# VISHIPEL_ver1_2.net
KiCad netlist of a schematic drawn in Altium Designer
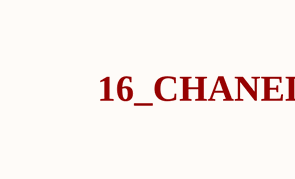
[diagram p0: VISHIPEL_ver1.2.SchDoc, top left]
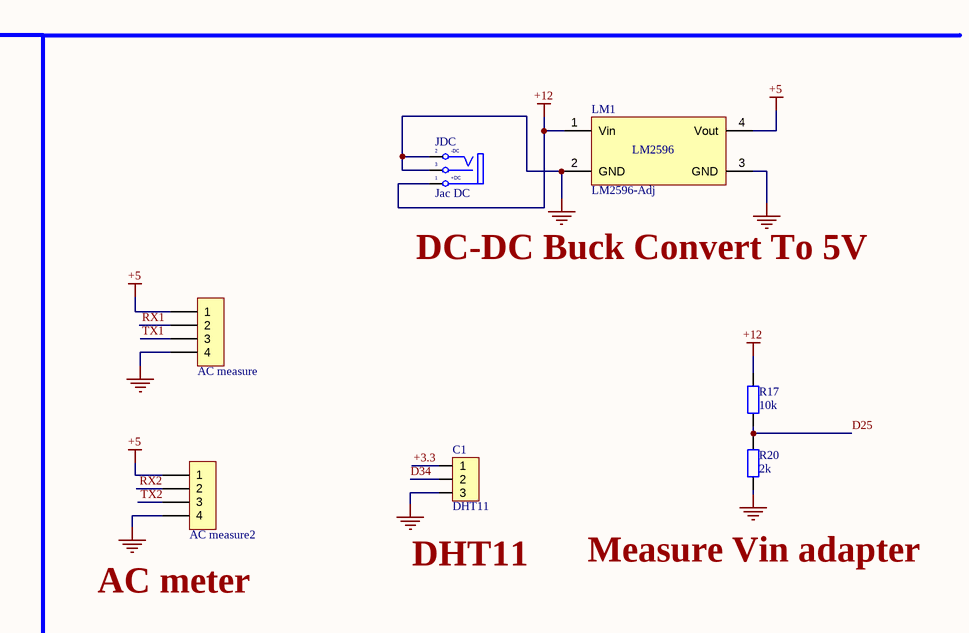
[diagram p1: VISHIPEL_ver1.2.SchDoc, top right]
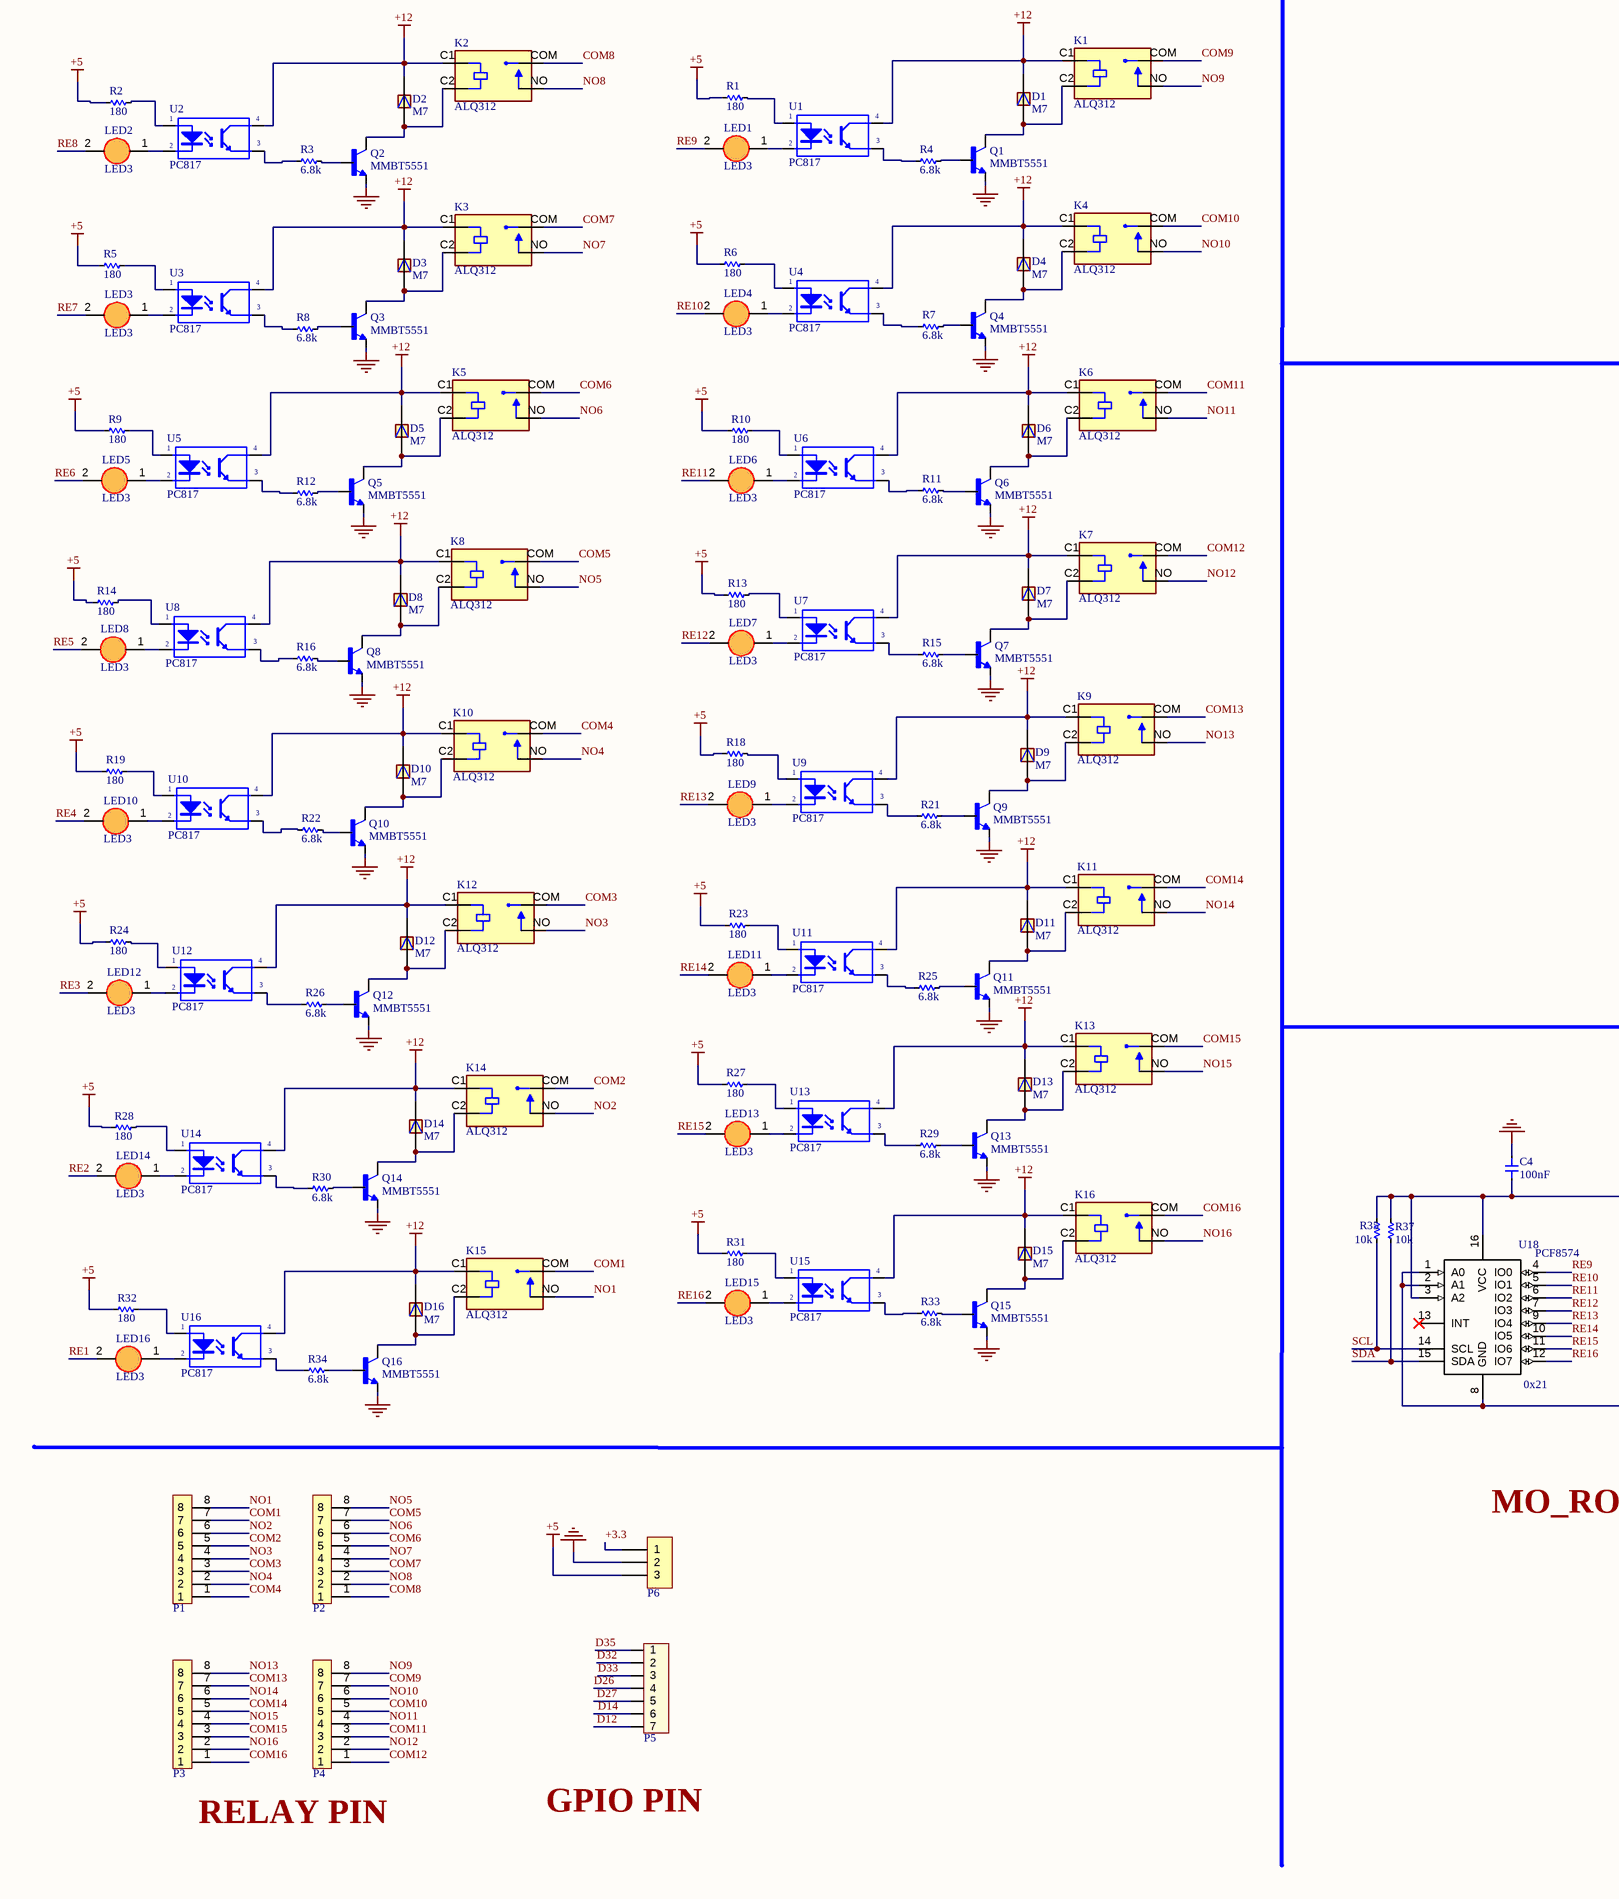
[diagram p2: VISHIPEL_ver1.2.SchDoc, bottom left]
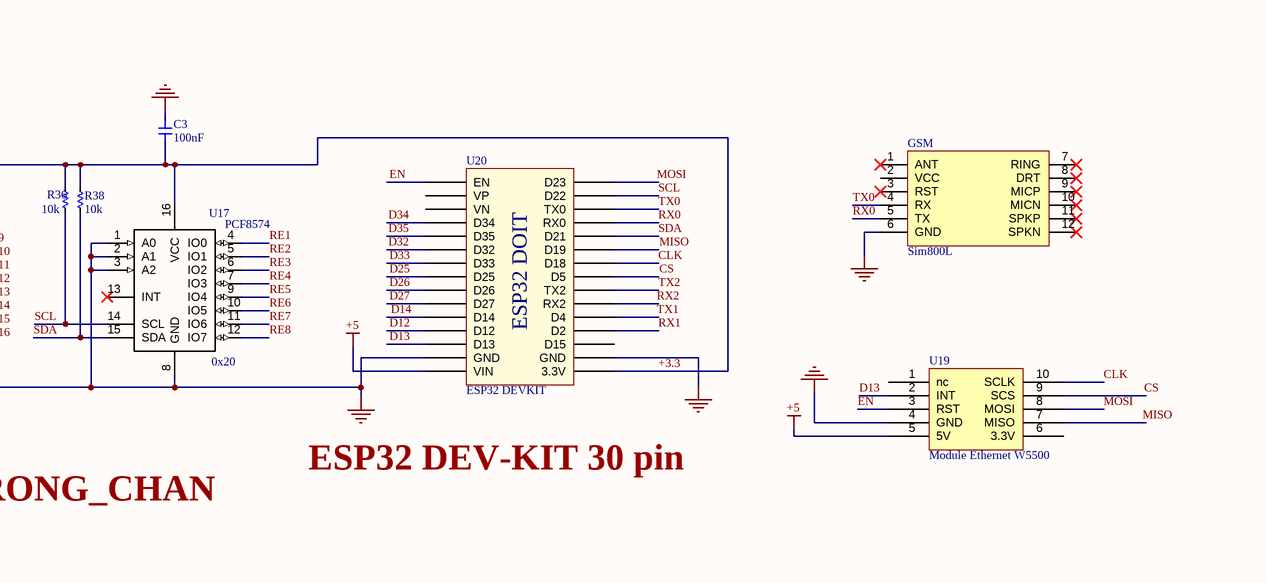
[diagram p3: VISHIPEL_ver1.2.SchDoc, bottom right]

(export (version "E")
  (design (tool "Eeschema 10.0.6"))
  (components
    (comp (ref "C1")
      (value "DHT11")
      (footprint "Header3")
      (description "Header IDC, 3 x 1 Pin Vertical 2.54mm Pitch (Non-Boxed, Male)")
      (fields
        (field (name "MANUFACTURER") "Würth Elektronik eiSos GmbH")
        (field (name "PARTNO") "613002143121")
        (field (name "CREATED BY") "Karrer Zheng")
      )
      (libsource (lib "My Library") (part "Header3"))
    )
    (comp (ref "C3")
      (value "100nF")
      (footprint "Cap 0805")
      (description "Capacitor SMD 0805")
      (libsource (lib "Altium_Lib_by_KhueNguyenCreator") (part "Cap 0805"))
    )
    (comp (ref "C4")
      (value "100nF")
      (footprint "Cap 0805")
      (description "Capacitor SMD 0805")
      (libsource (lib "Altium_Lib_by_KhueNguyenCreator") (part "Cap 0805"))
    )
    (comp (ref "D1")
      (value "M7")
      (footprint "DIOM505270X240")
      (description "Diode, SMA, 1000V, 1A, 150Â°C")
      (fields (field (name "MF") "Diotec Semiconductor"))
      (libsource (lib "M7") (part "M7"))
    )
    (comp (ref "D2")
      (value "M7")
      (footprint "DIOM505270X240")
      (description "Diode, SMA, 1000V, 1A, 150Â°C")
      (fields (field (name "MF") "Diotec Semiconductor"))
      (libsource (lib "M7") (part "M7"))
    )
    (comp (ref "D3")
      (value "M7")
      (footprint "DIOM505270X240")
      (description "Diode, SMA, 1000V, 1A, 150Â°C")
      (fields (field (name "MF") "Diotec Semiconductor"))
      (libsource (lib "M7") (part "M7"))
    )
    (comp (ref "D4")
      (value "M7")
      (footprint "DIOM505270X240")
      (description "Diode, SMA, 1000V, 1A, 150Â°C")
      (fields (field (name "MF") "Diotec Semiconductor"))
      (libsource (lib "M7") (part "M7"))
    )
    (comp (ref "D5")
      (value "M7")
      (footprint "DIOM505270X240")
      (description "Diode, SMA, 1000V, 1A, 150Â°C")
      (fields (field (name "MF") "Diotec Semiconductor"))
      (libsource (lib "M7") (part "M7"))
    )
    (comp (ref "D6")
      (value "M7")
      (footprint "DIOM505270X240")
      (description "Diode, SMA, 1000V, 1A, 150Â°C")
      (fields (field (name "MF") "Diotec Semiconductor"))
      (libsource (lib "M7") (part "M7"))
    )
    (comp (ref "D7")
      (value "M7")
      (footprint "DIOM505270X240")
      (description "Diode, SMA, 1000V, 1A, 150Â°C")
      (fields (field (name "MF") "Diotec Semiconductor"))
      (libsource (lib "M7") (part "M7"))
    )
    (comp (ref "D8")
      (value "M7")
      (footprint "DIOM505270X240")
      (description "Diode, SMA, 1000V, 1A, 150Â°C")
      (fields (field (name "MF") "Diotec Semiconductor"))
      (libsource (lib "M7") (part "M7"))
    )
    (comp (ref "D9")
      (value "M7")
      (footprint "DIOM505270X240")
      (description "Diode, SMA, 1000V, 1A, 150Â°C")
      (fields (field (name "MF") "Diotec Semiconductor"))
      (libsource (lib "M7") (part "M7"))
    )
    (comp (ref "D10")
      (value "M7")
      (footprint "DIOM505270X240")
      (description "Diode, SMA, 1000V, 1A, 150Â°C")
      (fields (field (name "MF") "Diotec Semiconductor"))
      (libsource (lib "M7") (part "M7"))
    )
    (comp (ref "D11")
      (value "M7")
      (footprint "DIOM505270X240")
      (description "Diode, SMA, 1000V, 1A, 150Â°C")
      (fields (field (name "MF") "Diotec Semiconductor"))
      (libsource (lib "M7") (part "M7"))
    )
    (comp (ref "D12")
      (value "M7")
      (footprint "DIOM505270X240")
      (description "Diode, SMA, 1000V, 1A, 150Â°C")
      (fields (field (name "MF") "Diotec Semiconductor"))
      (libsource (lib "M7") (part "M7"))
    )
    (comp (ref "D13")
      (value "M7")
      (footprint "DIOM505270X240")
      (description "Diode, SMA, 1000V, 1A, 150Â°C")
      (fields (field (name "MF") "Diotec Semiconductor"))
      (libsource (lib "M7") (part "M7"))
    )
    (comp (ref "D14")
      (value "M7")
      (footprint "DIOM505270X240")
      (description "Diode, SMA, 1000V, 1A, 150Â°C")
      (fields (field (name "MF") "Diotec Semiconductor"))
      (libsource (lib "M7") (part "M7"))
    )
    (comp (ref "D15")
      (value "M7")
      (footprint "DIOM505270X240")
      (description "Diode, SMA, 1000V, 1A, 150Â°C")
      (fields (field (name "MF") "Diotec Semiconductor"))
      (libsource (lib "M7") (part "M7"))
    )
    (comp (ref "D16")
      (value "M7")
      (footprint "DIOM505270X240")
      (description "Diode, SMA, 1000V, 1A, 150Â°C")
      (fields (field (name "MF") "Diotec Semiconductor"))
      (libsource (lib "M7") (part "M7"))
    )
    (comp (ref "GSM")
      (value "Sim800L")
      (footprint "Sim800L")
      (libsource (lib "Sim800L_Module") (part "Sim800L"))
    )
    (comp (ref "H1")
      (value "AC measure")
      (footprint "XH2.54M-4")
      (description "Cắm")
      (libsource (lib "Altium_Lib_by_KhueNguyenCreator") (part "Header 4P 2.54 Duc Thang"))
    )
    (comp (ref "H2")
      (value "AC measure2")
      (footprint "XH2.54M-4")
      (description "Cắm")
      (libsource (lib "Altium_Lib_by_KhueNguyenCreator") (part "Header 4P 2.54 Duc Thang"))
    )
    (comp (ref "H3")
      (value "P6")
      (footprint "VH3.96M-3")
      (description "Cắm")
      (libsource (lib "Altium_Lib_by_KhueNguyenCreator") (part "Header 3P VH3.96 Duc Thang"))
    )
    (comp (ref "H4")
      (value "P5")
      (footprint "VH3.96M-7")
      (description "Cắm")
      (libsource (lib "Altium_Lib_by_KhueNguyenCreator") (part "Header 7P VH3.96 Duc Thang"))
    )
    (comp (ref "JDC")
      (value "Jac DC")
      (footprint "DC-IN")
      (description "Jac DC input")
      (libsource (lib "Cty1") (part "DCIN"))
    )
    (comp (ref "K1")
      (value "ALQ312")
      (footprint "RELAY_ALQ312")
      (description "General Purpose Relay SPST-NO (1 Form A) 12VDC Coil Through Hole")
      (fields (field (name "MF") "Panasonic Electric"))
      (libsource (lib "ALQ312") (part "ALQ312"))
    )
    (comp (ref "K2")
      (value "ALQ312")
      (footprint "RELAY_ALQ312")
      (description "General Purpose Relay SPST-NO (1 Form A) 12VDC Coil Through Hole")
      (fields (field (name "MF") "Panasonic Electric"))
      (libsource (lib "ALQ312") (part "ALQ312"))
    )
    (comp (ref "K3")
      (value "ALQ312")
      (footprint "RELAY_ALQ312")
      (description "General Purpose Relay SPST-NO (1 Form A) 12VDC Coil Through Hole")
      (fields (field (name "MF") "Panasonic Electric"))
      (libsource (lib "ALQ312") (part "ALQ312"))
    )
    (comp (ref "K4")
      (value "ALQ312")
      (footprint "RELAY_ALQ312")
      (description "General Purpose Relay SPST-NO (1 Form A) 12VDC Coil Through Hole")
      (fields (field (name "MF") "Panasonic Electric"))
      (libsource (lib "ALQ312") (part "ALQ312"))
    )
    (comp (ref "K5")
      (value "ALQ312")
      (footprint "RELAY_ALQ312")
      (description "General Purpose Relay SPST-NO (1 Form A) 12VDC Coil Through Hole")
      (fields (field (name "MF") "Panasonic Electric"))
      (libsource (lib "ALQ312") (part "ALQ312"))
    )
    (comp (ref "K6")
      (value "ALQ312")
      (footprint "RELAY_ALQ312")
      (description "General Purpose Relay SPST-NO (1 Form A) 12VDC Coil Through Hole")
      (fields (field (name "MF") "Panasonic Electric"))
      (libsource (lib "ALQ312") (part "ALQ312"))
    )
    (comp (ref "K7")
      (value "ALQ312")
      (footprint "RELAY_ALQ312")
      (description "General Purpose Relay SPST-NO (1 Form A) 12VDC Coil Through Hole")
      (fields (field (name "MF") "Panasonic Electric"))
      (libsource (lib "ALQ312") (part "ALQ312"))
    )
    (comp (ref "K8")
      (value "ALQ312")
      (footprint "RELAY_ALQ312")
      (description "General Purpose Relay SPST-NO (1 Form A) 12VDC Coil Through Hole")
      (fields (field (name "MF") "Panasonic Electric"))
      (libsource (lib "ALQ312") (part "ALQ312"))
    )
    (comp (ref "K9")
      (value "ALQ312")
      (footprint "RELAY_ALQ312")
      (description "General Purpose Relay SPST-NO (1 Form A) 12VDC Coil Through Hole")
      (fields (field (name "MF") "Panasonic Electric"))
      (libsource (lib "ALQ312") (part "ALQ312"))
    )
    (comp (ref "K10")
      (value "ALQ312")
      (footprint "RELAY_ALQ312")
      (description "General Purpose Relay SPST-NO (1 Form A) 12VDC Coil Through Hole")
      (fields (field (name "MF") "Panasonic Electric"))
      (libsource (lib "ALQ312") (part "ALQ312"))
    )
    (comp (ref "K11")
      (value "ALQ312")
      (footprint "RELAY_ALQ312")
      (description "General Purpose Relay SPST-NO (1 Form A) 12VDC Coil Through Hole")
      (fields (field (name "MF") "Panasonic Electric"))
      (libsource (lib "ALQ312") (part "ALQ312"))
    )
    (comp (ref "K12")
      (value "ALQ312")
      (footprint "RELAY_ALQ312")
      (description "General Purpose Relay SPST-NO (1 Form A) 12VDC Coil Through Hole")
      (fields (field (name "MF") "Panasonic Electric"))
      (libsource (lib "ALQ312") (part "ALQ312"))
    )
    (comp (ref "K13")
      (value "ALQ312")
      (footprint "RELAY_ALQ312")
      (description "General Purpose Relay SPST-NO (1 Form A) 12VDC Coil Through Hole")
      (fields (field (name "MF") "Panasonic Electric"))
      (libsource (lib "ALQ312") (part "ALQ312"))
    )
    (comp (ref "K14")
      (value "ALQ312")
      (footprint "RELAY_ALQ312")
      (description "General Purpose Relay SPST-NO (1 Form A) 12VDC Coil Through Hole")
      (fields (field (name "MF") "Panasonic Electric"))
      (libsource (lib "ALQ312") (part "ALQ312"))
    )
    (comp (ref "K15")
      (value "ALQ312")
      (footprint "RELAY_ALQ312")
      (description "General Purpose Relay SPST-NO (1 Form A) 12VDC Coil Through Hole")
      (fields (field (name "MF") "Panasonic Electric"))
      (libsource (lib "ALQ312") (part "ALQ312"))
    )
    (comp (ref "K16")
      (value "ALQ312")
      (footprint "RELAY_ALQ312")
      (description "General Purpose Relay SPST-NO (1 Form A) 12VDC Coil Through Hole")
      (fields (field (name "MF") "Panasonic Electric"))
      (libsource (lib "ALQ312") (part "ALQ312"))
    )
    (comp (ref "LED1")
      (value "LED3")
      (footprint "LED3mm")
      (description "LED 3mm")
      (libsource (lib "My Library") (part "LED 3mm"))
    )
    (comp (ref "LED2")
      (value "LED3")
      (footprint "LED3mm")
      (description "LED 3mm")
      (libsource (lib "My Library") (part "LED 3mm"))
    )
    (comp (ref "LED3")
      (value "LED3")
      (footprint "LED3mm")
      (description "LED 3mm")
      (libsource (lib "My Library") (part "LED 3mm"))
    )
    (comp (ref "LED4")
      (value "LED3")
      (footprint "LED3mm")
      (description "LED 3mm")
      (libsource (lib "My Library") (part "LED 3mm"))
    )
    (comp (ref "LED5")
      (value "LED3")
      (footprint "LED3mm")
      (description "LED 3mm")
      (libsource (lib "My Library") (part "LED 3mm"))
    )
    (comp (ref "LED6")
      (value "LED3")
      (footprint "LED3mm")
      (description "LED 3mm")
      (libsource (lib "My Library") (part "LED 3mm"))
    )
    (comp (ref "LED7")
      (value "LED3")
      (footprint "LED3mm")
      (description "LED 3mm")
      (libsource (lib "My Library") (part "LED 3mm"))
    )
    (comp (ref "LED8")
      (value "LED3")
      (footprint "LED3mm")
      (description "LED 3mm")
      (libsource (lib "My Library") (part "LED 3mm"))
    )
    (comp (ref "LED9")
      (value "LED3")
      (footprint "LED3mm")
      (description "LED 3mm")
      (libsource (lib "My Library") (part "LED 3mm"))
    )
    (comp (ref "LED10")
      (value "LED3")
      (footprint "LED3mm")
      (description "LED 3mm")
      (libsource (lib "My Library") (part "LED 3mm"))
    )
    (comp (ref "LED11")
      (value "LED3")
      (footprint "LED3mm")
      (description "LED 3mm")
      (libsource (lib "My Library") (part "LED 3mm"))
    )
    (comp (ref "LED12")
      (value "LED3")
      (footprint "LED3mm")
      (description "LED 3mm")
      (libsource (lib "My Library") (part "LED 3mm"))
    )
    (comp (ref "LED13")
      (value "LED3")
      (footprint "LED3mm")
      (description "LED 3mm")
      (libsource (lib "My Library") (part "LED 3mm"))
    )
    (comp (ref "LED14")
      (value "LED3")
      (footprint "LED3mm")
      (description "LED 3mm")
      (libsource (lib "My Library") (part "LED 3mm"))
    )
    (comp (ref "LED15")
      (value "LED3")
      (footprint "LED3mm")
      (description "LED 3mm")
      (libsource (lib "My Library") (part "LED 3mm"))
    )
    (comp (ref "LED16")
      (value "LED3")
      (footprint "LED3mm")
      (description "LED 3mm")
      (libsource (lib "My Library") (part "LED 3mm"))
    )
    (comp (ref "LM1")
      (value "LM2596-Adj")
      (footprint "lm2596")
      (description "Designed By @Alixahedi")
      (libsource (lib "LM2596-Adj") (part "LM2596-Adj"))
    )
    (comp (ref "P1")
      (value "BIG Heager 8")
      (footprint "BIG_Header 8")
      (libsource (lib "Cty1") (part "BIG_Header 8"))
    )
    (comp (ref "P2")
      (value "BIG Heager 8")
      (footprint "BIG_Header 8")
      (libsource (lib "Cty1") (part "BIG_Header 8"))
    )
    (comp (ref "P3")
      (value "BIG Heager 8")
      (footprint "BIG_Header 8")
      (libsource (lib "Cty1") (part "BIG_Header 8"))
    )
    (comp (ref "P4")
      (value "BIG Heager 8")
      (footprint "BIG_Header 8")
      (libsource (lib "Cty1") (part "BIG_Header 8"))
    )
    (comp (ref "Q1")
      (value "MMBT5551")
      (footprint "SOT23-3")
      (fields (field (name "MF") "Fairchild Semiconductor"))
      (libsource (lib "MMBT5551") (part "MMBT5551"))
    )
    (comp (ref "Q2")
      (value "MMBT5551")
      (footprint "SOT23-3")
      (fields (field (name "MF") "Fairchild Semiconductor"))
      (libsource (lib "MMBT5551") (part "MMBT5551"))
    )
    (comp (ref "Q3")
      (value "MMBT5551")
      (footprint "SOT23-3")
      (fields (field (name "MF") "Fairchild Semiconductor"))
      (libsource (lib "MMBT5551") (part "MMBT5551"))
    )
    (comp (ref "Q4")
      (value "MMBT5551")
      (footprint "SOT23-3")
      (fields (field (name "MF") "Fairchild Semiconductor"))
      (libsource (lib "MMBT5551") (part "MMBT5551"))
    )
    (comp (ref "Q5")
      (value "MMBT5551")
      (footprint "SOT23-3")
      (fields (field (name "MF") "Fairchild Semiconductor"))
      (libsource (lib "MMBT5551") (part "MMBT5551"))
    )
    (comp (ref "Q6")
      (value "MMBT5551")
      (footprint "SOT23-3")
      (fields (field (name "MF") "Fairchild Semiconductor"))
      (libsource (lib "MMBT5551") (part "MMBT5551"))
    )
    (comp (ref "Q7")
      (value "MMBT5551")
      (footprint "SOT23-3")
      (fields (field (name "MF") "Fairchild Semiconductor"))
      (libsource (lib "MMBT5551") (part "MMBT5551"))
    )
    (comp (ref "Q8")
      (value "MMBT5551")
      (footprint "SOT23-3")
      (fields (field (name "MF") "Fairchild Semiconductor"))
      (libsource (lib "MMBT5551") (part "MMBT5551"))
    )
    (comp (ref "Q9")
      (value "MMBT5551")
      (footprint "SOT23-3")
      (fields (field (name "MF") "Fairchild Semiconductor"))
      (libsource (lib "MMBT5551") (part "MMBT5551"))
    )
    (comp (ref "Q10")
      (value "MMBT5551")
      (footprint "SOT23-3")
      (fields (field (name "MF") "Fairchild Semiconductor"))
      (libsource (lib "MMBT5551") (part "MMBT5551"))
    )
    (comp (ref "Q11")
      (value "MMBT5551")
      (footprint "SOT23-3")
      (fields (field (name "MF") "Fairchild Semiconductor"))
      (libsource (lib "MMBT5551") (part "MMBT5551"))
    )
    (comp (ref "Q12")
      (value "MMBT5551")
      (footprint "SOT23-3")
      (fields (field (name "MF") "Fairchild Semiconductor"))
      (libsource (lib "MMBT5551") (part "MMBT5551"))
    )
    (comp (ref "Q13")
      (value "MMBT5551")
      (footprint "SOT23-3")
      (fields (field (name "MF") "Fairchild Semiconductor"))
      (libsource (lib "MMBT5551") (part "MMBT5551"))
    )
    (comp (ref "Q14")
      (value "MMBT5551")
      (footprint "SOT23-3")
      (fields (field (name "MF") "Fairchild Semiconductor"))
      (libsource (lib "MMBT5551") (part "MMBT5551"))
    )
    (comp (ref "Q15")
      (value "MMBT5551")
      (footprint "SOT23-3")
      (fields (field (name "MF") "Fairchild Semiconductor"))
      (libsource (lib "MMBT5551") (part "MMBT5551"))
    )
    (comp (ref "Q16")
      (value "MMBT5551")
      (footprint "SOT23-3")
      (fields (field (name "MF") "Fairchild Semiconductor"))
      (libsource (lib "MMBT5551") (part "MMBT5551"))
    )
    (comp (ref "R1")
      (value "180")
      (footprint "RES-SMD-0101")
      (description "Resistor")
      (fields
        (field (name "MANUFACTURER") "Generic Components")
        (field (name "PUBLISHER") "Altium Hobart Technology Centre")
      )
      (libsource (lib "My Library") (part "Res-SMD"))
    )
    (comp (ref "R2")
      (value "180")
      (footprint "RES-SMD-0101")
      (description "Resistor")
      (fields
        (field (name "MANUFACTURER") "Generic Components")
        (field (name "PUBLISHER") "Altium Hobart Technology Centre")
      )
      (libsource (lib "My Library") (part "Res-SMD"))
    )
    (comp (ref "R3")
      (value "6.8k")
      (footprint "RES-SMD-0101")
      (description "Resistor")
      (fields
        (field (name "MANUFACTURER") "Generic Components")
        (field (name "PUBLISHER") "Altium Hobart Technology Centre")
      )
      (libsource (lib "My Library") (part "Res-SMD"))
    )
    (comp (ref "R4")
      (value "6.8k")
      (footprint "RES-SMD-0101")
      (description "Resistor")
      (fields
        (field (name "MANUFACTURER") "Generic Components")
        (field (name "PUBLISHER") "Altium Hobart Technology Centre")
      )
      (libsource (lib "My Library") (part "Res-SMD"))
    )
    (comp (ref "R5")
      (value "180")
      (footprint "RES-SMD-0101")
      (description "Resistor")
      (fields
        (field (name "MANUFACTURER") "Generic Components")
        (field (name "PUBLISHER") "Altium Hobart Technology Centre")
      )
      (libsource (lib "My Library") (part "Res-SMD"))
    )
    (comp (ref "R6")
      (value "180")
      (footprint "RES-SMD-0101")
      (description "Resistor")
      (fields
        (field (name "MANUFACTURER") "Generic Components")
        (field (name "PUBLISHER") "Altium Hobart Technology Centre")
      )
      (libsource (lib "My Library") (part "Res-SMD"))
    )
    (comp (ref "R7")
      (value "6.8k")
      (footprint "RES-SMD-0101")
      (description "Resistor")
      (fields
        (field (name "MANUFACTURER") "Generic Components")
        (field (name "PUBLISHER") "Altium Hobart Technology Centre")
      )
      (libsource (lib "My Library") (part "Res-SMD"))
    )
    (comp (ref "R8")
      (value "6.8k")
      (footprint "RES-SMD-0101")
      (description "Resistor")
      (fields
        (field (name "MANUFACTURER") "Generic Components")
        (field (name "PUBLISHER") "Altium Hobart Technology Centre")
      )
      (libsource (lib "My Library") (part "Res-SMD"))
    )
    (comp (ref "R9")
      (value "180")
      (footprint "RES-SMD-0101")
      (description "Resistor")
      (fields
        (field (name "MANUFACTURER") "Generic Components")
        (field (name "PUBLISHER") "Altium Hobart Technology Centre")
      )
      (libsource (lib "My Library") (part "Res-SMD"))
    )
    (comp (ref "R10")
      (value "180")
      (footprint "RES-SMD-0101")
      (description "Resistor")
      (fields
        (field (name "MANUFACTURER") "Generic Components")
        (field (name "PUBLISHER") "Altium Hobart Technology Centre")
      )
      (libsource (lib "My Library") (part "Res-SMD"))
    )
    (comp (ref "R11")
      (value "6.8k")
      (footprint "RES-SMD-0101")
      (description "Resistor")
      (fields
        (field (name "MANUFACTURER") "Generic Components")
        (field (name "PUBLISHER") "Altium Hobart Technology Centre")
      )
      (libsource (lib "My Library") (part "Res-SMD"))
    )
    (comp (ref "R12")
      (value "6.8k")
      (footprint "RES-SMD-0101")
      (description "Resistor")
      (fields
        (field (name "MANUFACTURER") "Generic Components")
        (field (name "PUBLISHER") "Altium Hobart Technology Centre")
      )
      (libsource (lib "My Library") (part "Res-SMD"))
    )
    (comp (ref "R13")
      (value "180")
      (footprint "RES-SMD-0101")
      (description "Resistor")
      (fields
        (field (name "MANUFACTURER") "Generic Components")
        (field (name "PUBLISHER") "Altium Hobart Technology Centre")
      )
      (libsource (lib "My Library") (part "Res-SMD"))
    )
    (comp (ref "R14")
      (value "180")
      (footprint "RES-SMD-0101")
      (description "Resistor")
      (fields
        (field (name "MANUFACTURER") "Generic Components")
        (field (name "PUBLISHER") "Altium Hobart Technology Centre")
      )
      (libsource (lib "My Library") (part "Res-SMD"))
    )
    (comp (ref "R15")
      (value "6.8k")
      (footprint "RES-SMD-0101")
      (description "Resistor")
      (fields
        (field (name "MANUFACTURER") "Generic Components")
        (field (name "PUBLISHER") "Altium Hobart Technology Centre")
      )
      (libsource (lib "My Library") (part "Res-SMD"))
    )
    (comp (ref "R16")
      (value "6.8k")
      (footprint "RES-SMD-0101")
      (description "Resistor")
      (fields
        (field (name "MANUFACTURER") "Generic Components")
        (field (name "PUBLISHER") "Altium Hobart Technology Centre")
      )
      (libsource (lib "My Library") (part "Res-SMD"))
    )
    (comp (ref "R17")
      (value "10k")
      (footprint "DIEN TRO 1/4 W")
      (description "Resistor")
      (fields (field (name "Comment") "R0.4W") (field (name "PUBLISHER") "Altium Limited"))
      (libsource (lib "My Library") (part "Res 1/4 W"))
    )
    (comp (ref "R18")
      (value "180")
      (footprint "RES-SMD-0101")
      (description "Resistor")
      (fields
        (field (name "MANUFACTURER") "Generic Components")
        (field (name "PUBLISHER") "Altium Hobart Technology Centre")
      )
      (libsource (lib "My Library") (part "Res-SMD"))
    )
    (comp (ref "R19")
      (value "180")
      (footprint "RES-SMD-0101")
      (description "Resistor")
      (fields
        (field (name "MANUFACTURER") "Generic Components")
        (field (name "PUBLISHER") "Altium Hobart Technology Centre")
      )
      (libsource (lib "My Library") (part "Res-SMD"))
    )
    (comp (ref "R20")
      (value "2k")
      (footprint "DIEN TRO 1/4 W")
      (description "Resistor")
      (fields (field (name "Comment") "R0.4W") (field (name "PUBLISHER") "Altium Limited"))
      (libsource (lib "My Library") (part "Res 1/4 W"))
    )
    (comp (ref "R21")
      (value "6.8k")
      (footprint "RES-SMD-0101")
      (description "Resistor")
      (fields
        (field (name "MANUFACTURER") "Generic Components")
        (field (name "PUBLISHER") "Altium Hobart Technology Centre")
      )
      (libsource (lib "My Library") (part "Res-SMD"))
    )
    (comp (ref "R22")
      (value "6.8k")
      (footprint "RES-SMD-0101")
      (description "Resistor")
      (fields
        (field (name "MANUFACTURER") "Generic Components")
        (field (name "PUBLISHER") "Altium Hobart Technology Centre")
      )
      (libsource (lib "My Library") (part "Res-SMD"))
    )
    (comp (ref "R23")
      (value "180")
      (footprint "RES-SMD-0101")
      (description "Resistor")
      (fields
        (field (name "MANUFACTURER") "Generic Components")
        (field (name "PUBLISHER") "Altium Hobart Technology Centre")
      )
      (libsource (lib "My Library") (part "Res-SMD"))
    )
    (comp (ref "R24")
      (value "180")
      (footprint "RES-SMD-0101")
      (description "Resistor")
      (fields
        (field (name "MANUFACTURER") "Generic Components")
        (field (name "PUBLISHER") "Altium Hobart Technology Centre")
      )
      (libsource (lib "My Library") (part "Res-SMD"))
    )
    (comp (ref "R25")
      (value "6.8k")
      (footprint "RES-SMD-0101")
      (description "Resistor")
      (fields
        (field (name "MANUFACTURER") "Generic Components")
        (field (name "PUBLISHER") "Altium Hobart Technology Centre")
      )
      (libsource (lib "My Library") (part "Res-SMD"))
    )
    (comp (ref "R26")
      (value "6.8k")
      (footprint "RES-SMD-0101")
      (description "Resistor")
      (fields
        (field (name "MANUFACTURER") "Generic Components")
        (field (name "PUBLISHER") "Altium Hobart Technology Centre")
      )
      (libsource (lib "My Library") (part "Res-SMD"))
    )
    (comp (ref "R27")
      (value "180")
      (footprint "RES-SMD-0101")
      (description "Resistor")
      (fields
        (field (name "MANUFACTURER") "Generic Components")
        (field (name "PUBLISHER") "Altium Hobart Technology Centre")
      )
      (libsource (lib "My Library") (part "Res-SMD"))
    )
    (comp (ref "R28")
      (value "180")
      (footprint "RES-SMD-0101")
      (description "Resistor")
      (fields
        (field (name "MANUFACTURER") "Generic Components")
        (field (name "PUBLISHER") "Altium Hobart Technology Centre")
      )
      (libsource (lib "My Library") (part "Res-SMD"))
    )
    (comp (ref "R29")
      (value "6.8k")
      (footprint "RES-SMD-0101")
      (description "Resistor")
      (fields
        (field (name "MANUFACTURER") "Generic Components")
        (field (name "PUBLISHER") "Altium Hobart Technology Centre")
      )
      (libsource (lib "My Library") (part "Res-SMD"))
    )
    (comp (ref "R30")
      (value "6.8k")
      (footprint "RES-SMD-0101")
      (description "Resistor")
      (fields
        (field (name "MANUFACTURER") "Generic Components")
        (field (name "PUBLISHER") "Altium Hobart Technology Centre")
      )
      (libsource (lib "My Library") (part "Res-SMD"))
    )
    (comp (ref "R31")
      (value "180")
      (footprint "RES-SMD-0101")
      (description "Resistor")
      (fields
        (field (name "MANUFACTURER") "Generic Components")
        (field (name "PUBLISHER") "Altium Hobart Technology Centre")
      )
      (libsource (lib "My Library") (part "Res-SMD"))
    )
    (comp (ref "R32")
      (value "180")
      (footprint "RES-SMD-0101")
      (description "Resistor")
      (fields
        (field (name "MANUFACTURER") "Generic Components")
        (field (name "PUBLISHER") "Altium Hobart Technology Centre")
      )
      (libsource (lib "My Library") (part "Res-SMD"))
    )
    (comp (ref "R33")
      (value "6.8k")
      (footprint "RES-SMD-0101")
      (description "Resistor")
      (fields
        (field (name "MANUFACTURER") "Generic Components")
        (field (name "PUBLISHER") "Altium Hobart Technology Centre")
      )
      (libsource (lib "My Library") (part "Res-SMD"))
    )
    (comp (ref "R34")
      (value "6.8k")
      (footprint "RES-SMD-0101")
      (description "Resistor")
      (fields
        (field (name "MANUFACTURER") "Generic Components")
        (field (name "PUBLISHER") "Altium Hobart Technology Centre")
      )
      (libsource (lib "My Library") (part "Res-SMD"))
    )
    (comp (ref "R35")
      (value "10k")
      (footprint "RES-SMD-0101")
      (description "Resistor")
      (fields
        (field (name "MANUFACTURER") "Generic Components")
        (field (name "PUBLISHER") "Altium Hobart Technology Centre")
      )
      (libsource (lib "My Library") (part "Res-SMD"))
    )
    (comp (ref "R36")
      (value "10k")
      (footprint "RES-SMD-0101")
      (description "Resistor")
      (fields
        (field (name "MANUFACTURER") "Generic Components")
        (field (name "PUBLISHER") "Altium Hobart Technology Centre")
      )
      (libsource (lib "My Library") (part "Res-SMD"))
    )
    (comp (ref "R37")
      (value "10k")
      (footprint "RES-SMD-0101")
      (description "Resistor")
      (fields
        (field (name "MANUFACTURER") "Generic Components")
        (field (name "PUBLISHER") "Altium Hobart Technology Centre")
      )
      (libsource (lib "My Library") (part "Res-SMD"))
    )
    (comp (ref "R38")
      (value "10k")
      (footprint "RES-SMD-0101")
      (description "Resistor")
      (fields
        (field (name "MANUFACTURER") "Generic Components")
        (field (name "PUBLISHER") "Altium Hobart Technology Centre")
      )
      (libsource (lib "My Library") (part "Res-SMD"))
    )
    (comp (ref "U1")
      (value "PC817")
      (footprint "DIP4/W0.3")
      (description "Single Opto")
      (libsource (lib "My Library") (part "PC817"))
    )
    (comp (ref "U2")
      (value "PC817")
      (footprint "DIP4/W0.3")
      (description "Single Opto")
      (libsource (lib "My Library") (part "PC817"))
    )
    (comp (ref "U3")
      (value "PC817")
      (footprint "DIP4/W0.3")
      (description "Single Opto")
      (libsource (lib "My Library") (part "PC817"))
    )
    (comp (ref "U4")
      (value "PC817")
      (footprint "DIP4/W0.3")
      (description "Single Opto")
      (libsource (lib "My Library") (part "PC817"))
    )
    (comp (ref "U5")
      (value "PC817")
      (footprint "DIP4/W0.3")
      (description "Single Opto")
      (libsource (lib "My Library") (part "PC817"))
    )
    (comp (ref "U6")
      (value "PC817")
      (footprint "DIP4/W0.3")
      (description "Single Opto")
      (libsource (lib "My Library") (part "PC817"))
    )
    (comp (ref "U7")
      (value "PC817")
      (footprint "DIP4/W0.3")
      (description "Single Opto")
      (libsource (lib "My Library") (part "PC817"))
    )
    (comp (ref "U8")
      (value "PC817")
      (footprint "DIP4/W0.3")
      (description "Single Opto")
      (libsource (lib "My Library") (part "PC817"))
    )
    (comp (ref "U9")
      (value "PC817")
      (footprint "DIP4/W0.3")
      (description "Single Opto")
      (libsource (lib "My Library") (part "PC817"))
    )
    (comp (ref "U10")
      (value "PC817")
      (footprint "DIP4/W0.3")
      (description "Single Opto")
      (libsource (lib "My Library") (part "PC817"))
    )
    (comp (ref "U11")
      (value "PC817")
      (footprint "DIP4/W0.3")
      (description "Single Opto")
      (libsource (lib "My Library") (part "PC817"))
    )
    (comp (ref "U12")
      (value "PC817")
      (footprint "DIP4/W0.3")
      (description "Single Opto")
      (libsource (lib "My Library") (part "PC817"))
    )
    (comp (ref "U13")
      (value "PC817")
      (footprint "DIP4/W0.3")
      (description "Single Opto")
      (libsource (lib "My Library") (part "PC817"))
    )
    (comp (ref "U14")
      (value "PC817")
      (footprint "DIP4/W0.3")
      (description "Single Opto")
      (libsource (lib "My Library") (part "PC817"))
    )
    (comp (ref "U15")
      (value "PC817")
      (footprint "DIP4/W0.3")
      (description "Single Opto")
      (libsource (lib "My Library") (part "PC817"))
    )
    (comp (ref "U16")
      (value "PC817")
      (footprint "DIP4/W0.3")
      (description "Single Opto")
      (libsource (lib "My Library") (part "PC817"))
    )
    (comp (ref "U17")
      (value "PCF8574")
      (footprint "DIP16")
      (description "I2C PORT EXPANDER")
      (fields
        (field (name "MANUFACTURER PART NUMBER") "PCF8574T/3,512")
        (field (name "MANUFACTURER") "NXP Semiconductors")
      )
      (libsource (lib "My Library") (part "PCF8574"))
    )
    (comp (ref "U18")
      (value "PCF8574")
      (footprint "DIP16")
      (description "I2C PORT EXPANDER")
      (fields
        (field (name "MANUFACTURER PART NUMBER") "PCF8574T/3,512")
        (field (name "MANUFACTURER") "NXP Semiconductors")
      )
      (libsource (lib "My Library") (part "PCF8574"))
    )
    (comp (ref "U19")
      (value "Module Ethernet W5500")
      (footprint "Module Ethernet W5500")
      (libsource (lib "Module Ethernet W5500") (part "Module Ethernet W5500"))
    )
    (comp (ref "U20")
      (value "ESP32 DEVKIT")
      (footprint "ESP32 WROOM 32 KIT")
      (libsource (lib "Altium_Lib_by_KhueNguyenCreator") (part "ESP32 WROOM 32 KIT"))
    )
  )
  (nets
    (net (code "1") (name "+5") (class "Default")
      (node (ref "H1") (pin "1") (pinfunction "1_1") (pintype "passive"))
      (node (ref "H2") (pin "1") (pinfunction "1_1") (pintype "passive"))
      (node (ref "H3") (pin "3") (pinfunction "3_3") (pintype "passive"))
      (node (ref "LM1") (pin "4") (pinfunction "Vout_4") (pintype "passive"))
      (node (ref "R1") (pin "1") (pinfunction "1_1") (pintype "passive"))
      (node (ref "R10") (pin "1") (pinfunction "1_1") (pintype "passive"))
      (node (ref "R13") (pin "1") (pinfunction "1_1") (pintype "passive"))
      (node (ref "R14") (pin "1") (pinfunction "1_1") (pintype "passive"))
      (node (ref "R18") (pin "1") (pinfunction "1_1") (pintype "passive"))
      (node (ref "R19") (pin "1") (pinfunction "1_1") (pintype "passive"))
      (node (ref "R2") (pin "1") (pinfunction "1_1") (pintype "passive"))
      (node (ref "R23") (pin "1") (pinfunction "1_1") (pintype "passive"))
      (node (ref "R24") (pin "1") (pinfunction "1_1") (pintype "passive"))
      (node (ref "R27") (pin "1") (pinfunction "1_1") (pintype "passive"))
      (node (ref "R28") (pin "1") (pinfunction "1_1") (pintype "passive"))
      (node (ref "R31") (pin "1") (pinfunction "1_1") (pintype "passive"))
      (node (ref "R32") (pin "1") (pinfunction "1_1") (pintype "passive"))
      (node (ref "R5") (pin "1") (pinfunction "1_1") (pintype "passive"))
      (node (ref "R6") (pin "1") (pinfunction "1_1") (pintype "passive"))
      (node (ref "R9") (pin "1") (pinfunction "1_1") (pintype "passive"))
      (node (ref "U19") (pin "5") (pinfunction "5V_5") (pintype "passive"))
      (node (ref "U20") (pin "15") (pinfunction "VIN_15") (pintype "passive"))
    )
    (net (code "2") (name "+12") (class "Default")
      (node (ref "D1") (pin "C") (pinfunction "C_C") (pintype "passive"))
      (node (ref "D10") (pin "C") (pinfunction "C_C") (pintype "passive"))
      (node (ref "D11") (pin "C") (pinfunction "C_C") (pintype "passive"))
      (node (ref "D12") (pin "C") (pinfunction "C_C") (pintype "passive"))
      (node (ref "D13") (pin "C") (pinfunction "C_C") (pintype "passive"))
      (node (ref "D14") (pin "C") (pinfunction "C_C") (pintype "passive"))
      (node (ref "D15") (pin "C") (pinfunction "C_C") (pintype "passive"))
      (node (ref "D16") (pin "C") (pinfunction "C_C") (pintype "passive"))
      (node (ref "D2") (pin "C") (pinfunction "C_C") (pintype "passive"))
      (node (ref "D3") (pin "C") (pinfunction "C_C") (pintype "passive"))
      (node (ref "D4") (pin "C") (pinfunction "C_C") (pintype "passive"))
      (node (ref "D5") (pin "C") (pinfunction "C_C") (pintype "passive"))
      (node (ref "D6") (pin "C") (pinfunction "C_C") (pintype "passive"))
      (node (ref "D7") (pin "C") (pinfunction "C_C") (pintype "passive"))
      (node (ref "D8") (pin "C") (pinfunction "C_C") (pintype "passive"))
      (node (ref "D9") (pin "C") (pinfunction "C_C") (pintype "passive"))
      (node (ref "JDC") (pin "1") (pinfunction "T_1") (pintype "passive"))
      (node (ref "K1") (pin "C1") (pinfunction "COIL1_C1") (pintype "passive"))
      (node (ref "K10") (pin "C1") (pinfunction "COIL1_C1") (pintype "passive"))
      (node (ref "K11") (pin "C1") (pinfunction "COIL1_C1") (pintype "passive"))
      (node (ref "K12") (pin "C1") (pinfunction "COIL1_C1") (pintype "passive"))
      (node (ref "K13") (pin "C1") (pinfunction "COIL1_C1") (pintype "passive"))
      (node (ref "K14") (pin "C1") (pinfunction "COIL1_C1") (pintype "passive"))
      (node (ref "K15") (pin "C1") (pinfunction "COIL1_C1") (pintype "passive"))
      (node (ref "K16") (pin "C1") (pinfunction "COIL1_C1") (pintype "passive"))
      (node (ref "K2") (pin "C1") (pinfunction "COIL1_C1") (pintype "passive"))
      (node (ref "K3") (pin "C1") (pinfunction "COIL1_C1") (pintype "passive"))
      (node (ref "K4") (pin "C1") (pinfunction "COIL1_C1") (pintype "passive"))
      (node (ref "K5") (pin "C1") (pinfunction "COIL1_C1") (pintype "passive"))
      (node (ref "K6") (pin "C1") (pinfunction "COIL1_C1") (pintype "passive"))
      (node (ref "K7") (pin "C1") (pinfunction "COIL1_C1") (pintype "passive"))
      (node (ref "K8") (pin "C1") (pinfunction "COIL1_C1") (pintype "passive"))
      (node (ref "K9") (pin "C1") (pinfunction "COIL1_C1") (pintype "passive"))
      (node (ref "LM1") (pin "1") (pinfunction "Vin_1") (pintype "passive"))
      (node (ref "R17") (pin "2") (pinfunction "2_2") (pintype "passive"))
      (node (ref "U1") (pin "4") (pinfunction "C_4") (pintype "passive"))
      (node (ref "U10") (pin "4") (pinfunction "C_4") (pintype "passive"))
      (node (ref "U11") (pin "4") (pinfunction "C_4") (pintype "passive"))
      (node (ref "U12") (pin "4") (pinfunction "C_4") (pintype "passive"))
      (node (ref "U13") (pin "4") (pinfunction "C_4") (pintype "passive"))
      (node (ref "U14") (pin "4") (pinfunction "C_4") (pintype "passive"))
      (node (ref "U15") (pin "4") (pinfunction "C_4") (pintype "passive"))
      (node (ref "U16") (pin "4") (pinfunction "C_4") (pintype "passive"))
      (node (ref "U2") (pin "4") (pinfunction "C_4") (pintype "passive"))
      (node (ref "U3") (pin "4") (pinfunction "C_4") (pintype "passive"))
      (node (ref "U4") (pin "4") (pinfunction "C_4") (pintype "passive"))
      (node (ref "U5") (pin "4") (pinfunction "C_4") (pintype "passive"))
      (node (ref "U6") (pin "4") (pinfunction "C_4") (pintype "passive"))
      (node (ref "U7") (pin "4") (pinfunction "C_4") (pintype "passive"))
      (node (ref "U8") (pin "4") (pinfunction "C_4") (pintype "passive"))
      (node (ref "U9") (pin "4") (pinfunction "C_4") (pintype "passive"))
    )
    (net (code "3") (name "/+3.3") (class "Default")
      (node (ref "C1") (pin "1") (pinfunction "1_1") (pintype "passive"))
      (node (ref "C3") (pin "2") (pinfunction "2_2") (pintype "passive"))
      (node (ref "C4") (pin "2") (pinfunction "2_2") (pintype "passive"))
      (node (ref "H3") (pin "1") (pinfunction "1_1") (pintype "passive"))
      (node (ref "R35") (pin "1") (pinfunction "1_1") (pintype "passive"))
      (node (ref "R36") (pin "1") (pinfunction "1_1") (pintype "passive"))
      (node (ref "R37") (pin "1") (pinfunction "1_1") (pintype "passive"))
      (node (ref "R38") (pin "1") (pinfunction "1_1") (pintype "passive"))
      (node (ref "U17") (pin "16") (pinfunction "VCC_16") (pintype "passive"))
      (node (ref "U18") (pin "16") (pinfunction "VCC_16") (pintype "passive"))
      (node (ref "U18") (pin "3") (pinfunction "A2_3") (pintype "input"))
      (node (ref "U20") (pin "16") (pinfunction "3.3V_16") (pintype "passive"))
    )
    (net (code "5") (name "/CLK") (class "Default")
      (node (ref "U19") (pin "10") (pinfunction "SCLK_10") (pintype "passive"))
      (node (ref "U20") (pin "24") (pinfunction "D18_24") (pintype "passive"))
    )
    (net (code "6") (name "/COM1") (class "Default")
      (node (ref "K15") (pin "COM") (pinfunction "COM_COM") (pintype "passive"))
      (node (ref "P1") (pin "7") (pinfunction "7_7") (pintype "passive"))
    )
    (net (code "7") (name "/COM2") (class "Default")
      (node (ref "K14") (pin "COM") (pinfunction "COM_COM") (pintype "passive"))
      (node (ref "P1") (pin "5") (pinfunction "5_5") (pintype "passive"))
    )
    (net (code "8") (name "/COM3") (class "Default")
      (node (ref "K12") (pin "COM") (pinfunction "COM_COM") (pintype "passive"))
      (node (ref "P1") (pin "3") (pinfunction "3_3") (pintype "passive"))
    )
    (net (code "9") (name "/COM4") (class "Default")
      (node (ref "K10") (pin "COM") (pinfunction "COM_COM") (pintype "passive"))
      (node (ref "P1") (pin "1") (pinfunction "1_1") (pintype "passive"))
    )
    (net (code "10") (name "/COM5") (class "Default")
      (node (ref "K8") (pin "COM") (pinfunction "COM_COM") (pintype "passive"))
      (node (ref "P2") (pin "7") (pinfunction "7_7") (pintype "passive"))
    )
    (net (code "11") (name "/COM6") (class "Default")
      (node (ref "K5") (pin "COM") (pinfunction "COM_COM") (pintype "passive"))
      (node (ref "P2") (pin "5") (pinfunction "5_5") (pintype "passive"))
    )
    (net (code "12") (name "/COM7") (class "Default")
      (node (ref "K3") (pin "COM") (pinfunction "COM_COM") (pintype "passive"))
      (node (ref "P2") (pin "3") (pinfunction "3_3") (pintype "passive"))
    )
    (net (code "13") (name "/COM8") (class "Default")
      (node (ref "K2") (pin "COM") (pinfunction "COM_COM") (pintype "passive"))
      (node (ref "P2") (pin "1") (pinfunction "1_1") (pintype "passive"))
    )
    (net (code "14") (name "/COM9") (class "Default")
      (node (ref "K1") (pin "COM") (pinfunction "COM_COM") (pintype "passive"))
      (node (ref "P4") (pin "7") (pinfunction "7_7") (pintype "passive"))
    )
    (net (code "15") (name "/COM10") (class "Default")
      (node (ref "K4") (pin "COM") (pinfunction "COM_COM") (pintype "passive"))
      (node (ref "P4") (pin "5") (pinfunction "5_5") (pintype "passive"))
    )
    (net (code "16") (name "/COM11") (class "Default")
      (node (ref "K6") (pin "COM") (pinfunction "COM_COM") (pintype "passive"))
      (node (ref "P4") (pin "3") (pinfunction "3_3") (pintype "passive"))
    )
    (net (code "17") (name "/COM12") (class "Default")
      (node (ref "K7") (pin "COM") (pinfunction "COM_COM") (pintype "passive"))
      (node (ref "P4") (pin "1") (pinfunction "1_1") (pintype "passive"))
    )
    (net (code "18") (name "/COM13") (class "Default")
      (node (ref "K9") (pin "COM") (pinfunction "COM_COM") (pintype "passive"))
      (node (ref "P3") (pin "7") (pinfunction "7_7") (pintype "passive"))
    )
    (net (code "19") (name "/COM14") (class "Default")
      (node (ref "K11") (pin "COM") (pinfunction "COM_COM") (pintype "passive"))
      (node (ref "P3") (pin "5") (pinfunction "5_5") (pintype "passive"))
    )
    (net (code "20") (name "/COM15") (class "Default")
      (node (ref "K13") (pin "COM") (pinfunction "COM_COM") (pintype "passive"))
      (node (ref "P3") (pin "3") (pinfunction "3_3") (pintype "passive"))
    )
    (net (code "21") (name "/COM16") (class "Default")
      (node (ref "K16") (pin "COM") (pinfunction "COM_COM") (pintype "passive"))
      (node (ref "P3") (pin "1") (pinfunction "1_1") (pintype "passive"))
    )
    (net (code "22") (name "/CS") (class "Default")
      (node (ref "U19") (pin "9") (pinfunction "SCS_9") (pintype "passive"))
      (node (ref "U20") (pin "23") (pinfunction "D5_23") (pintype "passive"))
    )
    (net (code "23") (name "/D12") (class "Default")
      (node (ref "H4") (pin "7") (pinfunction "7_7") (pintype "passive"))
      (node (ref "U20") (pin "12") (pinfunction "D12_12") (pintype "passive"))
    )
    (net (code "24") (name "/D13") (class "Default")
      (node (ref "U19") (pin "2") (pinfunction "INT_2") (pintype "passive"))
      (node (ref "U20") (pin "13") (pinfunction "D13_13") (pintype "passive"))
    )
    (net (code "25") (name "/D14") (class "Default")
      (node (ref "H4") (pin "6") (pinfunction "6_6") (pintype "passive"))
      (node (ref "U20") (pin "11") (pinfunction "D14_11") (pintype "passive"))
    )
    (net (code "26") (name "/D25") (class "Default")
      (node (ref "R17") (pin "1") (pinfunction "1_1") (pintype "passive"))
      (node (ref "R20") (pin "2") (pinfunction "2_2") (pintype "passive"))
      (node (ref "U20") (pin "8") (pinfunction "D25_8") (pintype "passive"))
    )
    (net (code "27") (name "/D26") (class "Default")
      (node (ref "H4") (pin "4") (pinfunction "4_4") (pintype "passive"))
      (node (ref "U20") (pin "9") (pinfunction "D26_9") (pintype "passive"))
    )
    (net (code "28") (name "/D27") (class "Default")
      (node (ref "H4") (pin "5") (pinfunction "5_5") (pintype "passive"))
      (node (ref "U20") (pin "10") (pinfunction "D27_10") (pintype "passive"))
    )
    (net (code "29") (name "/D32") (class "Default")
      (node (ref "H4") (pin "2") (pinfunction "2_2") (pintype "passive"))
      (node (ref "U20") (pin "6") (pinfunction "D32_6") (pintype "passive"))
    )
    (net (code "30") (name "/D33") (class "Default")
      (node (ref "H4") (pin "3") (pinfunction "3_3") (pintype "passive"))
      (node (ref "U20") (pin "7") (pinfunction "D33_7") (pintype "passive"))
    )
    (net (code "31") (name "/D34") (class "Default")
      (node (ref "C1") (pin "2") (pinfunction "2_2") (pintype "passive"))
      (node (ref "U20") (pin "4") (pinfunction "D34_4") (pintype "passive"))
    )
    (net (code "32") (name "/D35") (class "Default")
      (node (ref "H4") (pin "1") (pinfunction "1_1") (pintype "passive"))
      (node (ref "U20") (pin "5") (pinfunction "D35_5") (pintype "passive"))
    )
    (net (code "33") (name "/EN") (class "Default")
      (node (ref "U19") (pin "3") (pinfunction "RST_3") (pintype "passive"))
      (node (ref "U20") (pin "1") (pinfunction "EN_1") (pintype "passive"))
    )
    (net (code "34") (name "/MISO") (class "Default")
      (node (ref "U19") (pin "7") (pinfunction "MISO_7") (pintype "passive"))
      (node (ref "U20") (pin "25") (pinfunction "D19_25") (pintype "passive"))
    )
    (net (code "35") (name "/MOSI") (class "Default")
      (node (ref "U19") (pin "8") (pinfunction "MOSI_8") (pintype "passive"))
      (node (ref "U20") (pin "30") (pinfunction "D23_30") (pintype "passive"))
    )
    (net (code "36") (name "/NO1") (class "Default")
      (node (ref "K15") (pin "NO") (pinfunction "NO_NO") (pintype "passive"))
      (node (ref "P1") (pin "8") (pinfunction "8_8") (pintype "passive"))
    )
    (net (code "37") (name "/NO2") (class "Default")
      (node (ref "K14") (pin "NO") (pinfunction "NO_NO") (pintype "passive"))
      (node (ref "P1") (pin "6") (pinfunction "6_6") (pintype "passive"))
    )
    (net (code "38") (name "/NO3") (class "Default")
      (node (ref "K12") (pin "NO") (pinfunction "NO_NO") (pintype "passive"))
      (node (ref "P1") (pin "4") (pinfunction "4_4") (pintype "passive"))
    )
    (net (code "39") (name "/NO4") (class "Default")
      (node (ref "K10") (pin "NO") (pinfunction "NO_NO") (pintype "passive"))
      (node (ref "P1") (pin "2") (pinfunction "2_2") (pintype "passive"))
    )
    (net (code "40") (name "/NO5") (class "Default")
      (node (ref "K8") (pin "NO") (pinfunction "NO_NO") (pintype "passive"))
      (node (ref "P2") (pin "8") (pinfunction "8_8") (pintype "passive"))
    )
    (net (code "41") (name "/NO6") (class "Default")
      (node (ref "K5") (pin "NO") (pinfunction "NO_NO") (pintype "passive"))
      (node (ref "P2") (pin "6") (pinfunction "6_6") (pintype "passive"))
    )
    (net (code "42") (name "/NO7") (class "Default")
      (node (ref "K3") (pin "NO") (pinfunction "NO_NO") (pintype "passive"))
      (node (ref "P2") (pin "4") (pinfunction "4_4") (pintype "passive"))
    )
    (net (code "43") (name "/NO8") (class "Default")
      (node (ref "K2") (pin "NO") (pinfunction "NO_NO") (pintype "passive"))
      (node (ref "P2") (pin "2") (pinfunction "2_2") (pintype "passive"))
    )
    (net (code "44") (name "/NO9") (class "Default")
      (node (ref "K1") (pin "NO") (pinfunction "NO_NO") (pintype "passive"))
      (node (ref "P4") (pin "8") (pinfunction "8_8") (pintype "passive"))
    )
    (net (code "45") (name "/NO10") (class "Default")
      (node (ref "K4") (pin "NO") (pinfunction "NO_NO") (pintype "passive"))
      (node (ref "P4") (pin "6") (pinfunction "6_6") (pintype "passive"))
    )
    (net (code "46") (name "/NO11") (class "Default")
      (node (ref "K6") (pin "NO") (pinfunction "NO_NO") (pintype "passive"))
      (node (ref "P4") (pin "4") (pinfunction "4_4") (pintype "passive"))
    )
    (net (code "47") (name "/NO12") (class "Default")
      (node (ref "K7") (pin "NO") (pinfunction "NO_NO") (pintype "passive"))
      (node (ref "P4") (pin "2") (pinfunction "2_2") (pintype "passive"))
    )
    (net (code "48") (name "/NO13") (class "Default")
      (node (ref "K9") (pin "NO") (pinfunction "NO_NO") (pintype "passive"))
      (node (ref "P3") (pin "8") (pinfunction "8_8") (pintype "passive"))
    )
    (net (code "49") (name "/NO14") (class "Default")
      (node (ref "K11") (pin "NO") (pinfunction "NO_NO") (pintype "passive"))
      (node (ref "P3") (pin "6") (pinfunction "6_6") (pintype "passive"))
    )
    (net (code "50") (name "/NO15") (class "Default")
      (node (ref "K13") (pin "NO") (pinfunction "NO_NO") (pintype "passive"))
      (node (ref "P3") (pin "4") (pinfunction "4_4") (pintype "passive"))
    )
    (net (code "51") (name "/NO16") (class "Default")
      (node (ref "K16") (pin "NO") (pinfunction "NO_NO") (pintype "passive"))
      (node (ref "P3") (pin "2") (pinfunction "2_2") (pintype "passive"))
    )
    (net (code "52") (name "/RE1") (class "Default")
      (node (ref "LED16") (pin "2") (pinfunction "K_2") (pintype "passive"))
      (node (ref "U17") (pin "4") (pinfunction "IO0_4") (pintype "bidirectional"))
    )
    (net (code "53") (name "/RE2") (class "Default")
      (node (ref "LED14") (pin "2") (pinfunction "K_2") (pintype "passive"))
      (node (ref "U17") (pin "5") (pinfunction "IO1_5") (pintype "bidirectional"))
    )
    (net (code "54") (name "/RE3") (class "Default")
      (node (ref "LED12") (pin "2") (pinfunction "K_2") (pintype "passive"))
      (node (ref "U17") (pin "6") (pinfunction "IO2_6") (pintype "bidirectional"))
    )
    (net (code "55") (name "/RE4") (class "Default")
      (node (ref "LED10") (pin "2") (pinfunction "K_2") (pintype "passive"))
      (node (ref "U17") (pin "7") (pinfunction "IO3_7") (pintype "bidirectional"))
    )
    (net (code "56") (name "/RE5") (class "Default")
      (node (ref "LED8") (pin "2") (pinfunction "K_2") (pintype "passive"))
      (node (ref "U17") (pin "9") (pinfunction "IO4_9") (pintype "bidirectional"))
    )
    (net (code "57") (name "/RE6") (class "Default")
      (node (ref "LED5") (pin "2") (pinfunction "K_2") (pintype "passive"))
      (node (ref "U17") (pin "10") (pinfunction "IO5_10") (pintype "bidirectional"))
    )
    (net (code "58") (name "/RE7") (class "Default")
      (node (ref "LED3") (pin "2") (pinfunction "K_2") (pintype "passive"))
      (node (ref "U17") (pin "11") (pinfunction "IO6_11") (pintype "bidirectional"))
    )
    (net (code "59") (name "/RE8") (class "Default")
      (node (ref "LED2") (pin "2") (pinfunction "K_2") (pintype "passive"))
      (node (ref "U17") (pin "12") (pinfunction "IO7_12") (pintype "bidirectional"))
    )
    (net (code "60") (name "/RE9") (class "Default")
      (node (ref "LED1") (pin "2") (pinfunction "K_2") (pintype "passive"))
      (node (ref "U18") (pin "4") (pinfunction "IO0_4") (pintype "bidirectional"))
    )
    (net (code "61") (name "/RE10") (class "Default")
      (node (ref "LED4") (pin "2") (pinfunction "K_2") (pintype "passive"))
      (node (ref "U18") (pin "5") (pinfunction "IO1_5") (pintype "bidirectional"))
    )
    (net (code "62") (name "/RE11") (class "Default")
      (node (ref "LED6") (pin "2") (pinfunction "K_2") (pintype "passive"))
      (node (ref "U18") (pin "6") (pinfunction "IO2_6") (pintype "bidirectional"))
    )
    (net (code "63") (name "/RE12") (class "Default")
      (node (ref "LED7") (pin "2") (pinfunction "K_2") (pintype "passive"))
      (node (ref "U18") (pin "7") (pinfunction "IO3_7") (pintype "bidirectional"))
    )
    (net (code "64") (name "/RE13") (class "Default")
      (node (ref "LED9") (pin "2") (pinfunction "K_2") (pintype "passive"))
      (node (ref "U18") (pin "9") (pinfunction "IO4_9") (pintype "bidirectional"))
    )
    (net (code "65") (name "/RE14") (class "Default")
      (node (ref "LED11") (pin "2") (pinfunction "K_2") (pintype "passive"))
      (node (ref "U18") (pin "10") (pinfunction "IO5_10") (pintype "bidirectional"))
    )
    (net (code "66") (name "/RE15") (class "Default")
      (node (ref "LED13") (pin "2") (pinfunction "K_2") (pintype "passive"))
      (node (ref "U18") (pin "11") (pinfunction "IO6_11") (pintype "bidirectional"))
    )
    (net (code "67") (name "/RE16") (class "Default")
      (node (ref "LED15") (pin "2") (pinfunction "K_2") (pintype "passive"))
      (node (ref "U18") (pin "12") (pinfunction "IO7_12") (pintype "bidirectional"))
    )
    (net (code "68") (name "/RX0") (class "Default")
      (node (ref "GSM") (pin "5") (pinfunction "TX_5") (pintype "passive"))
      (node (ref "U20") (pin "27") (pinfunction "RX0_27") (pintype "passive"))
    )
    (net (code "69") (name "/RX1") (class "Default")
      (node (ref "H1") (pin "2") (pinfunction "2_2") (pintype "passive"))
      (node (ref "U20") (pin "19") (pinfunction "D2_19") (pintype "passive"))
    )
    (net (code "70") (name "/RX2") (class "Default")
      (node (ref "H2") (pin "2") (pinfunction "2_2") (pintype "passive"))
      (node (ref "U20") (pin "21") (pinfunction "RX2_21") (pintype "passive"))
    )
    (net (code "71") (name "/SCL") (class "Default")
      (node (ref "R35") (pin "2") (pinfunction "2_2") (pintype "passive"))
      (node (ref "R36") (pin "2") (pinfunction "2_2") (pintype "passive"))
      (node (ref "U17") (pin "14") (pinfunction "SCL_14") (pintype "open_collector"))
      (node (ref "U18") (pin "14") (pinfunction "SCL_14") (pintype "open_collector"))
      (node (ref "U20") (pin "29") (pinfunction "D22_29") (pintype "passive"))
    )
    (net (code "72") (name "/SDA") (class "Default")
      (node (ref "R37") (pin "2") (pinfunction "2_2") (pintype "passive"))
      (node (ref "R38") (pin "2") (pinfunction "2_2") (pintype "passive"))
      (node (ref "U17") (pin "15") (pinfunction "SDA_15") (pintype "open_collector"))
      (node (ref "U18") (pin "15") (pinfunction "SDA_15") (pintype "open_collector"))
      (node (ref "U20") (pin "26") (pinfunction "D21_26") (pintype "passive"))
    )
    (net (code "73") (name "/TX0") (class "Default")
      (node (ref "GSM") (pin "4") (pinfunction "RX_4") (pintype "passive"))
      (node (ref "U20") (pin "28") (pinfunction "TX0_28") (pintype "passive"))
    )
    (net (code "74") (name "/TX1") (class "Default")
      (node (ref "H1") (pin "3") (pinfunction "3_3") (pintype "passive"))
      (node (ref "U20") (pin "20") (pinfunction "D4_20") (pintype "passive"))
    )
    (net (code "75") (name "/TX2") (class "Default")
      (node (ref "H2") (pin "3") (pinfunction "3_3") (pintype "passive"))
      (node (ref "U20") (pin "22") (pinfunction "TX2_22") (pintype "passive"))
    )
    (net (code "76") (name "GND") (class "Default")
      (node (ref "C1") (pin "3") (pinfunction "3_3") (pintype "passive"))
      (node (ref "C3") (pin "1") (pinfunction "1_1") (pintype "passive"))
      (node (ref "C4") (pin "1") (pinfunction "1_1") (pintype "passive"))
      (node (ref "GSM") (pin "6") (pinfunction "GND_6") (pintype "passive"))
      (node (ref "H1") (pin "4") (pinfunction "4_4") (pintype "passive"))
      (node (ref "H2") (pin "4") (pinfunction "4_4") (pintype "passive"))
      (node (ref "H3") (pin "2") (pinfunction "2_2") (pintype "passive"))
      (node (ref "JDC") (pin "2") (pinfunction "TN_2") (pintype "passive"))
      (node (ref "JDC") (pin "3") (pinfunction "S_3") (pintype "power_in"))
      (node (ref "LM1") (pin "2") (pinfunction "GND_2") (pintype "passive"))
      (node (ref "LM1") (pin "3") (pinfunction "GND_3") (pintype "passive"))
      (node (ref "Q1") (pin "2") (pinfunction "E_2") (pintype "passive"))
      (node (ref "Q10") (pin "2") (pinfunction "E_2") (pintype "passive"))
      (node (ref "Q11") (pin "2") (pinfunction "E_2") (pintype "passive"))
      (node (ref "Q12") (pin "2") (pinfunction "E_2") (pintype "passive"))
      (node (ref "Q13") (pin "2") (pinfunction "E_2") (pintype "passive"))
      (node (ref "Q14") (pin "2") (pinfunction "E_2") (pintype "passive"))
      (node (ref "Q15") (pin "2") (pinfunction "E_2") (pintype "passive"))
      (node (ref "Q16") (pin "2") (pinfunction "E_2") (pintype "passive"))
      (node (ref "Q2") (pin "2") (pinfunction "E_2") (pintype "passive"))
      (node (ref "Q3") (pin "2") (pinfunction "E_2") (pintype "passive"))
      (node (ref "Q4") (pin "2") (pinfunction "E_2") (pintype "passive"))
      (node (ref "Q5") (pin "2") (pinfunction "E_2") (pintype "passive"))
      (node (ref "Q6") (pin "2") (pinfunction "E_2") (pintype "passive"))
      (node (ref "Q7") (pin "2") (pinfunction "E_2") (pintype "passive"))
      (node (ref "Q8") (pin "2") (pinfunction "E_2") (pintype "passive"))
      (node (ref "Q9") (pin "2") (pinfunction "E_2") (pintype "passive"))
      (node (ref "R20") (pin "1") (pinfunction "1_1") (pintype "passive"))
      (node (ref "U17") (pin "1") (pinfunction "A0_1") (pintype "input"))
      (node (ref "U17") (pin "2") (pinfunction "A1_2") (pintype "input"))
      (node (ref "U17") (pin "3") (pinfunction "A2_3") (pintype "input"))
      (node (ref "U17") (pin "8") (pinfunction "GND_8") (pintype "passive"))
      (node (ref "U18") (pin "1") (pinfunction "A0_1") (pintype "input"))
      (node (ref "U18") (pin "2") (pinfunction "A1_2") (pintype "input"))
      (node (ref "U18") (pin "8") (pinfunction "GND_8") (pintype "passive"))
      (node (ref "U19") (pin "4") (pinfunction "GND_4") (pintype "passive"))
      (node (ref "U20") (pin "14") (pinfunction "GND_14") (pintype "passive"))
      (node (ref "U20") (pin "17") (pinfunction "GND_17") (pintype "passive"))
    )
    (net (code "77") (name "Net-(K1-COIL2)") (class "Default")
      (node (ref "D1") (pin "A") (pinfunction "A_A") (pintype "passive"))
      (node (ref "K1") (pin "C2") (pinfunction "COIL2_C2") (pintype "passive"))
      (node (ref "Q1") (pin "3") (pinfunction "C_3") (pintype "passive"))
    )
    (net (code "78") (name "Net-(K2-COIL2)") (class "Default")
      (node (ref "D2") (pin "A") (pinfunction "A_A") (pintype "passive"))
      (node (ref "K2") (pin "C2") (pinfunction "COIL2_C2") (pintype "passive"))
      (node (ref "Q2") (pin "3") (pinfunction "C_3") (pintype "passive"))
    )
    (net (code "79") (name "Net-(K3-COIL2)") (class "Default")
      (node (ref "D3") (pin "A") (pinfunction "A_A") (pintype "passive"))
      (node (ref "K3") (pin "C2") (pinfunction "COIL2_C2") (pintype "passive"))
      (node (ref "Q3") (pin "3") (pinfunction "C_3") (pintype "passive"))
    )
    (net (code "80") (name "Net-(K4-COIL2)") (class "Default")
      (node (ref "D4") (pin "A") (pinfunction "A_A") (pintype "passive"))
      (node (ref "K4") (pin "C2") (pinfunction "COIL2_C2") (pintype "passive"))
      (node (ref "Q4") (pin "3") (pinfunction "C_3") (pintype "passive"))
    )
    (net (code "81") (name "Net-(K5-COIL2)") (class "Default")
      (node (ref "D5") (pin "A") (pinfunction "A_A") (pintype "passive"))
      (node (ref "K5") (pin "C2") (pinfunction "COIL2_C2") (pintype "passive"))
      (node (ref "Q5") (pin "3") (pinfunction "C_3") (pintype "passive"))
    )
    (net (code "82") (name "Net-(K6-COIL2)") (class "Default")
      (node (ref "D6") (pin "A") (pinfunction "A_A") (pintype "passive"))
      (node (ref "K6") (pin "C2") (pinfunction "COIL2_C2") (pintype "passive"))
      (node (ref "Q6") (pin "3") (pinfunction "C_3") (pintype "passive"))
    )
    (net (code "83") (name "Net-(K7-COIL2)") (class "Default")
      (node (ref "D7") (pin "A") (pinfunction "A_A") (pintype "passive"))
      (node (ref "K7") (pin "C2") (pinfunction "COIL2_C2") (pintype "passive"))
      (node (ref "Q7") (pin "3") (pinfunction "C_3") (pintype "passive"))
    )
    (net (code "84") (name "Net-(K8-COIL2)") (class "Default")
      (node (ref "D8") (pin "A") (pinfunction "A_A") (pintype "passive"))
      (node (ref "K8") (pin "C2") (pinfunction "COIL2_C2") (pintype "passive"))
      (node (ref "Q8") (pin "3") (pinfunction "C_3") (pintype "passive"))
    )
    (net (code "85") (name "Net-(K9-COIL2)") (class "Default")
      (node (ref "D9") (pin "A") (pinfunction "A_A") (pintype "passive"))
      (node (ref "K9") (pin "C2") (pinfunction "COIL2_C2") (pintype "passive"))
      (node (ref "Q9") (pin "3") (pinfunction "C_3") (pintype "passive"))
    )
    (net (code "86") (name "Net-(K10-COIL2)") (class "Default")
      (node (ref "D10") (pin "A") (pinfunction "A_A") (pintype "passive"))
      (node (ref "K10") (pin "C2") (pinfunction "COIL2_C2") (pintype "passive"))
      (node (ref "Q10") (pin "3") (pinfunction "C_3") (pintype "passive"))
    )
    (net (code "87") (name "Net-(K11-COIL2)") (class "Default")
      (node (ref "D11") (pin "A") (pinfunction "A_A") (pintype "passive"))
      (node (ref "K11") (pin "C2") (pinfunction "COIL2_C2") (pintype "passive"))
      (node (ref "Q11") (pin "3") (pinfunction "C_3") (pintype "passive"))
    )
    (net (code "88") (name "Net-(K12-COIL2)") (class "Default")
      (node (ref "D12") (pin "A") (pinfunction "A_A") (pintype "passive"))
      (node (ref "K12") (pin "C2") (pinfunction "COIL2_C2") (pintype "passive"))
      (node (ref "Q12") (pin "3") (pinfunction "C_3") (pintype "passive"))
    )
    (net (code "89") (name "Net-(K13-COIL2)") (class "Default")
      (node (ref "D13") (pin "A") (pinfunction "A_A") (pintype "passive"))
      (node (ref "K13") (pin "C2") (pinfunction "COIL2_C2") (pintype "passive"))
      (node (ref "Q13") (pin "3") (pinfunction "C_3") (pintype "passive"))
    )
    (net (code "90") (name "Net-(K14-COIL2)") (class "Default")
      (node (ref "D14") (pin "A") (pinfunction "A_A") (pintype "passive"))
      (node (ref "K14") (pin "C2") (pinfunction "COIL2_C2") (pintype "passive"))
      (node (ref "Q14") (pin "3") (pinfunction "C_3") (pintype "passive"))
    )
    (net (code "91") (name "Net-(K15-COIL2)") (class "Default")
      (node (ref "D16") (pin "A") (pinfunction "A_A") (pintype "passive"))
      (node (ref "K15") (pin "C2") (pinfunction "COIL2_C2") (pintype "passive"))
      (node (ref "Q16") (pin "3") (pinfunction "C_3") (pintype "passive"))
    )
    (net (code "92") (name "Net-(K16-COIL2)") (class "Default")
      (node (ref "D15") (pin "A") (pinfunction "A_A") (pintype "passive"))
      (node (ref "K16") (pin "C2") (pinfunction "COIL2_C2") (pintype "passive"))
      (node (ref "Q15") (pin "3") (pinfunction "C_3") (pintype "passive"))
    )
    (net (code "93") (name "Net-(LED1-A)") (class "Default")
      (node (ref "LED1") (pin "1") (pinfunction "A_1") (pintype "passive"))
      (node (ref "U1") (pin "2") (pinfunction "K_2") (pintype "passive"))
    )
    (net (code "94") (name "Net-(LED2-A)") (class "Default")
      (node (ref "LED2") (pin "1") (pinfunction "A_1") (pintype "passive"))
      (node (ref "U2") (pin "2") (pinfunction "K_2") (pintype "passive"))
    )
    (net (code "95") (name "Net-(LED3-A)") (class "Default")
      (node (ref "LED3") (pin "1") (pinfunction "A_1") (pintype "passive"))
      (node (ref "U3") (pin "2") (pinfunction "K_2") (pintype "passive"))
    )
    (net (code "96") (name "Net-(LED4-A)") (class "Default")
      (node (ref "LED4") (pin "1") (pinfunction "A_1") (pintype "passive"))
      (node (ref "U4") (pin "2") (pinfunction "K_2") (pintype "passive"))
    )
    (net (code "97") (name "Net-(LED5-A)") (class "Default")
      (node (ref "LED5") (pin "1") (pinfunction "A_1") (pintype "passive"))
      (node (ref "U5") (pin "2") (pinfunction "K_2") (pintype "passive"))
    )
    (net (code "98") (name "Net-(LED6-A)") (class "Default")
      (node (ref "LED6") (pin "1") (pinfunction "A_1") (pintype "passive"))
      (node (ref "U6") (pin "2") (pinfunction "K_2") (pintype "passive"))
    )
    (net (code "99") (name "Net-(LED7-A)") (class "Default")
      (node (ref "LED7") (pin "1") (pinfunction "A_1") (pintype "passive"))
      (node (ref "U7") (pin "2") (pinfunction "K_2") (pintype "passive"))
    )
    (net (code "100") (name "Net-(LED8-A)") (class "Default")
      (node (ref "LED8") (pin "1") (pinfunction "A_1") (pintype "passive"))
      (node (ref "U8") (pin "2") (pinfunction "K_2") (pintype "passive"))
    )
    (net (code "101") (name "Net-(LED9-A)") (class "Default")
      (node (ref "LED9") (pin "1") (pinfunction "A_1") (pintype "passive"))
      (node (ref "U9") (pin "2") (pinfunction "K_2") (pintype "passive"))
    )
    (net (code "102") (name "Net-(LED10-A)") (class "Default")
      (node (ref "LED10") (pin "1") (pinfunction "A_1") (pintype "passive"))
      (node (ref "U10") (pin "2") (pinfunction "K_2") (pintype "passive"))
    )
    (net (code "103") (name "Net-(LED11-A)") (class "Default")
      (node (ref "LED11") (pin "1") (pinfunction "A_1") (pintype "passive"))
      (node (ref "U11") (pin "2") (pinfunction "K_2") (pintype "passive"))
    )
    (net (code "104") (name "Net-(LED12-A)") (class "Default")
      (node (ref "LED12") (pin "1") (pinfunction "A_1") (pintype "passive"))
      (node (ref "U12") (pin "2") (pinfunction "K_2") (pintype "passive"))
    )
    (net (code "105") (name "Net-(LED13-A)") (class "Default")
      (node (ref "LED13") (pin "1") (pinfunction "A_1") (pintype "passive"))
      (node (ref "U13") (pin "2") (pinfunction "K_2") (pintype "passive"))
    )
    (net (code "106") (name "Net-(LED14-A)") (class "Default")
      (node (ref "LED14") (pin "1") (pinfunction "A_1") (pintype "passive"))
      (node (ref "U14") (pin "2") (pinfunction "K_2") (pintype "passive"))
    )
    (net (code "107") (name "Net-(LED15-A)") (class "Default")
      (node (ref "LED15") (pin "1") (pinfunction "A_1") (pintype "passive"))
      (node (ref "U15") (pin "2") (pinfunction "K_2") (pintype "passive"))
    )
    (net (code "108") (name "Net-(LED16-A)") (class "Default")
      (node (ref "LED16") (pin "1") (pinfunction "A_1") (pintype "passive"))
      (node (ref "U16") (pin "2") (pinfunction "K_2") (pintype "passive"))
    )
    (net (code "109") (name "Net-(Q1-B)") (class "Default")
      (node (ref "Q1") (pin "1") (pinfunction "B_1") (pintype "passive"))
      (node (ref "R4") (pin "2") (pinfunction "2_2") (pintype "passive"))
    )
    (net (code "110") (name "Net-(Q2-B)") (class "Default")
      (node (ref "Q2") (pin "1") (pinfunction "B_1") (pintype "passive"))
      (node (ref "R3") (pin "2") (pinfunction "2_2") (pintype "passive"))
    )
    (net (code "111") (name "Net-(Q3-B)") (class "Default")
      (node (ref "Q3") (pin "1") (pinfunction "B_1") (pintype "passive"))
      (node (ref "R8") (pin "2") (pinfunction "2_2") (pintype "passive"))
    )
    (net (code "112") (name "Net-(Q4-B)") (class "Default")
      (node (ref "Q4") (pin "1") (pinfunction "B_1") (pintype "passive"))
      (node (ref "R7") (pin "2") (pinfunction "2_2") (pintype "passive"))
    )
    (net (code "113") (name "Net-(Q5-B)") (class "Default")
      (node (ref "Q5") (pin "1") (pinfunction "B_1") (pintype "passive"))
      (node (ref "R12") (pin "2") (pinfunction "2_2") (pintype "passive"))
    )
    (net (code "114") (name "Net-(Q6-B)") (class "Default")
      (node (ref "Q6") (pin "1") (pinfunction "B_1") (pintype "passive"))
      (node (ref "R11") (pin "2") (pinfunction "2_2") (pintype "passive"))
    )
    (net (code "115") (name "Net-(Q7-B)") (class "Default")
      (node (ref "Q7") (pin "1") (pinfunction "B_1") (pintype "passive"))
      (node (ref "R15") (pin "2") (pinfunction "2_2") (pintype "passive"))
    )
    (net (code "116") (name "Net-(Q8-B)") (class "Default")
      (node (ref "Q8") (pin "1") (pinfunction "B_1") (pintype "passive"))
      (node (ref "R16") (pin "2") (pinfunction "2_2") (pintype "passive"))
    )
    (net (code "117") (name "Net-(Q9-B)") (class "Default")
      (node (ref "Q9") (pin "1") (pinfunction "B_1") (pintype "passive"))
      (node (ref "R21") (pin "2") (pinfunction "2_2") (pintype "passive"))
    )
    (net (code "118") (name "Net-(Q10-B)") (class "Default")
      (node (ref "Q10") (pin "1") (pinfunction "B_1") (pintype "passive"))
      (node (ref "R22") (pin "2") (pinfunction "2_2") (pintype "passive"))
    )
    (net (code "119") (name "Net-(Q11-B)") (class "Default")
      (node (ref "Q11") (pin "1") (pinfunction "B_1") (pintype "passive"))
      (node (ref "R25") (pin "2") (pinfunction "2_2") (pintype "passive"))
    )
    (net (code "120") (name "Net-(Q12-B)") (class "Default")
      (node (ref "Q12") (pin "1") (pinfunction "B_1") (pintype "passive"))
      (node (ref "R26") (pin "2") (pinfunction "2_2") (pintype "passive"))
    )
    (net (code "121") (name "Net-(Q13-B)") (class "Default")
      (node (ref "Q13") (pin "1") (pinfunction "B_1") (pintype "passive"))
      (node (ref "R29") (pin "2") (pinfunction "2_2") (pintype "passive"))
    )
    (net (code "122") (name "Net-(Q14-B)") (class "Default")
      (node (ref "Q14") (pin "1") (pinfunction "B_1") (pintype "passive"))
      (node (ref "R30") (pin "2") (pinfunction "2_2") (pintype "passive"))
    )
    (net (code "123") (name "Net-(Q15-B)") (class "Default")
      (node (ref "Q15") (pin "1") (pinfunction "B_1") (pintype "passive"))
      (node (ref "R33") (pin "2") (pinfunction "2_2") (pintype "passive"))
    )
    (net (code "124") (name "Net-(Q16-B)") (class "Default")
      (node (ref "Q16") (pin "1") (pinfunction "B_1") (pintype "passive"))
      (node (ref "R34") (pin "2") (pinfunction "2_2") (pintype "passive"))
    )
    (net (code "125") (name "Net-(U1-A)") (class "Default")
      (node (ref "R1") (pin "2") (pinfunction "2_2") (pintype "passive"))
      (node (ref "U1") (pin "1") (pinfunction "A_1") (pintype "passive"))
    )
    (net (code "126") (name "Net-(U1-E)") (class "Default")
      (node (ref "R4") (pin "1") (pinfunction "1_1") (pintype "passive"))
      (node (ref "U1") (pin "3") (pinfunction "E_3") (pintype "passive"))
    )
    (net (code "127") (name "Net-(U2-A)") (class "Default")
      (node (ref "R2") (pin "2") (pinfunction "2_2") (pintype "passive"))
      (node (ref "U2") (pin "1") (pinfunction "A_1") (pintype "passive"))
    )
    (net (code "128") (name "Net-(U2-E)") (class "Default")
      (node (ref "R3") (pin "1") (pinfunction "1_1") (pintype "passive"))
      (node (ref "U2") (pin "3") (pinfunction "E_3") (pintype "passive"))
    )
    (net (code "129") (name "Net-(U3-A)") (class "Default")
      (node (ref "R5") (pin "2") (pinfunction "2_2") (pintype "passive"))
      (node (ref "U3") (pin "1") (pinfunction "A_1") (pintype "passive"))
    )
    (net (code "130") (name "Net-(U3-E)") (class "Default")
      (node (ref "R8") (pin "1") (pinfunction "1_1") (pintype "passive"))
      (node (ref "U3") (pin "3") (pinfunction "E_3") (pintype "passive"))
    )
    (net (code "131") (name "Net-(U4-A)") (class "Default")
      (node (ref "R6") (pin "2") (pinfunction "2_2") (pintype "passive"))
      (node (ref "U4") (pin "1") (pinfunction "A_1") (pintype "passive"))
    )
    (net (code "132") (name "Net-(U4-E)") (class "Default")
      (node (ref "R7") (pin "1") (pinfunction "1_1") (pintype "passive"))
      (node (ref "U4") (pin "3") (pinfunction "E_3") (pintype "passive"))
    )
    (net (code "133") (name "Net-(U5-A)") (class "Default")
      (node (ref "R9") (pin "2") (pinfunction "2_2") (pintype "passive"))
      (node (ref "U5") (pin "1") (pinfunction "A_1") (pintype "passive"))
    )
    (net (code "134") (name "Net-(U5-E)") (class "Default")
      (node (ref "R12") (pin "1") (pinfunction "1_1") (pintype "passive"))
      (node (ref "U5") (pin "3") (pinfunction "E_3") (pintype "passive"))
    )
    (net (code "135") (name "Net-(U6-A)") (class "Default")
      (node (ref "R10") (pin "2") (pinfunction "2_2") (pintype "passive"))
      (node (ref "U6") (pin "1") (pinfunction "A_1") (pintype "passive"))
    )
    (net (code "136") (name "Net-(U6-E)") (class "Default")
      (node (ref "R11") (pin "1") (pinfunction "1_1") (pintype "passive"))
      (node (ref "U6") (pin "3") (pinfunction "E_3") (pintype "passive"))
    )
    (net (code "137") (name "Net-(U7-A)") (class "Default")
      (node (ref "R13") (pin "2") (pinfunction "2_2") (pintype "passive"))
      (node (ref "U7") (pin "1") (pinfunction "A_1") (pintype "passive"))
    )
    (net (code "138") (name "Net-(U7-E)") (class "Default")
      (node (ref "R15") (pin "1") (pinfunction "1_1") (pintype "passive"))
      (node (ref "U7") (pin "3") (pinfunction "E_3") (pintype "passive"))
    )
    (net (code "139") (name "Net-(U8-A)") (class "Default")
      (node (ref "R14") (pin "2") (pinfunction "2_2") (pintype "passive"))
      (node (ref "U8") (pin "1") (pinfunction "A_1") (pintype "passive"))
    )
    (net (code "140") (name "Net-(U8-E)") (class "Default")
      (node (ref "R16") (pin "1") (pinfunction "1_1") (pintype "passive"))
      (node (ref "U8") (pin "3") (pinfunction "E_3") (pintype "passive"))
    )
    (net (code "141") (name "Net-(U9-A)") (class "Default")
      (node (ref "R18") (pin "2") (pinfunction "2_2") (pintype "passive"))
      (node (ref "U9") (pin "1") (pinfunction "A_1") (pintype "passive"))
    )
    (net (code "142") (name "Net-(U9-E)") (class "Default")
      (node (ref "R21") (pin "1") (pinfunction "1_1") (pintype "passive"))
      (node (ref "U9") (pin "3") (pinfunction "E_3") (pintype "passive"))
    )
    (net (code "143") (name "Net-(U10-A)") (class "Default")
      (node (ref "R19") (pin "2") (pinfunction "2_2") (pintype "passive"))
      (node (ref "U10") (pin "1") (pinfunction "A_1") (pintype "passive"))
    )
    (net (code "144") (name "Net-(U10-E)") (class "Default")
      (node (ref "R22") (pin "1") (pinfunction "1_1") (pintype "passive"))
      (node (ref "U10") (pin "3") (pinfunction "E_3") (pintype "passive"))
    )
    (net (code "145") (name "Net-(U11-A)") (class "Default")
      (node (ref "R23") (pin "2") (pinfunction "2_2") (pintype "passive"))
      (node (ref "U11") (pin "1") (pinfunction "A_1") (pintype "passive"))
    )
    (net (code "146") (name "Net-(U11-E)") (class "Default")
      (node (ref "R25") (pin "1") (pinfunction "1_1") (pintype "passive"))
      (node (ref "U11") (pin "3") (pinfunction "E_3") (pintype "passive"))
    )
    (net (code "147") (name "Net-(U12-A)") (class "Default")
      (node (ref "R24") (pin "2") (pinfunction "2_2") (pintype "passive"))
      (node (ref "U12") (pin "1") (pinfunction "A_1") (pintype "passive"))
    )
    (net (code "148") (name "Net-(U12-E)") (class "Default")
      (node (ref "R26") (pin "1") (pinfunction "1_1") (pintype "passive"))
      (node (ref "U12") (pin "3") (pinfunction "E_3") (pintype "passive"))
    )
    (net (code "149") (name "Net-(U13-A)") (class "Default")
      (node (ref "R27") (pin "2") (pinfunction "2_2") (pintype "passive"))
      (node (ref "U13") (pin "1") (pinfunction "A_1") (pintype "passive"))
    )
    (net (code "150") (name "Net-(U13-E)") (class "Default")
      (node (ref "R29") (pin "1") (pinfunction "1_1") (pintype "passive"))
      (node (ref "U13") (pin "3") (pinfunction "E_3") (pintype "passive"))
    )
    (net (code "151") (name "Net-(U14-A)") (class "Default")
      (node (ref "R28") (pin "2") (pinfunction "2_2") (pintype "passive"))
      (node (ref "U14") (pin "1") (pinfunction "A_1") (pintype "passive"))
    )
    (net (code "152") (name "Net-(U14-E)") (class "Default")
      (node (ref "R30") (pin "1") (pinfunction "1_1") (pintype "passive"))
      (node (ref "U14") (pin "3") (pinfunction "E_3") (pintype "passive"))
    )
    (net (code "153") (name "Net-(U15-A)") (class "Default")
      (node (ref "R31") (pin "2") (pinfunction "2_2") (pintype "passive"))
      (node (ref "U15") (pin "1") (pinfunction "A_1") (pintype "passive"))
    )
    (net (code "154") (name "Net-(U15-E)") (class "Default")
      (node (ref "R33") (pin "1") (pinfunction "1_1") (pintype "passive"))
      (node (ref "U15") (pin "3") (pinfunction "E_3") (pintype "passive"))
    )
    (net (code "155") (name "Net-(U16-A)") (class "Default")
      (node (ref "R32") (pin "2") (pinfunction "2_2") (pintype "passive"))
      (node (ref "U16") (pin "1") (pinfunction "A_1") (pintype "passive"))
    )
    (net (code "156") (name "Net-(U16-E)") (class "Default")
      (node (ref "R34") (pin "1") (pinfunction "1_1") (pintype "passive"))
      (node (ref "U16") (pin "3") (pinfunction "E_3") (pintype "passive"))
    )
    (net (code "157") (name "unconnected-(GSM-ANT-Pad1)") (class "Default")
      (node (ref "GSM") (pin "1") (pinfunction "ANT_1") (pintype "passive+no_connect"))
    )
    (net (code "158") (name "unconnected-(GSM-DRT-Pad8)") (class "Default")
      (node (ref "GSM") (pin "8") (pinfunction "DRT_8") (pintype "passive+no_connect"))
    )
    (net (code "159") (name "unconnected-(GSM-MICN-Pad10)") (class "Default")
      (node (ref "GSM") (pin "10") (pinfunction "MICN_10") (pintype "passive+no_connect"))
    )
    (net (code "160") (name "unconnected-(GSM-MICP-Pad9)") (class "Default")
      (node (ref "GSM") (pin "9") (pinfunction "MICP_9") (pintype "passive+no_connect"))
    )
    (net (code "161") (name "unconnected-(GSM-RING-Pad7)") (class "Default")
      (node (ref "GSM") (pin "7") (pinfunction "RING_7") (pintype "passive+no_connect"))
    )
    (net (code "162") (name "unconnected-(GSM-RST-Pad3)") (class "Default")
      (node (ref "GSM") (pin "3") (pinfunction "RST_3") (pintype "passive+no_connect"))
    )
    (net (code "163") (name "unconnected-(GSM-SPKN-Pad12)") (class "Default")
      (node (ref "GSM") (pin "12") (pinfunction "SPKN_12") (pintype "passive+no_connect"))
    )
    (net (code "164") (name "unconnected-(GSM-SPKP-Pad11)") (class "Default")
      (node (ref "GSM") (pin "11") (pinfunction "SPKP_11") (pintype "passive+no_connect"))
    )
    (net (code "165") (name "unconnected-(GSM-VCC-Pad2)") (class "Default")
      (node (ref "GSM") (pin "2") (pinfunction "VCC_2") (pintype "passive"))
    )
    (net (code "166") (name "unconnected-(U17-INT-Pad13)") (class "Default")
      (node (ref "U17") (pin "13") (pinfunction "INT_13") (pintype "open_collector+no_connect"))
    )
    (net (code "167") (name "unconnected-(U18-INT-Pad13)") (class "Default")
      (node (ref "U18") (pin "13") (pinfunction "INT_13") (pintype "open_collector+no_connect"))
    )
    (net (code "168") (name "unconnected-(U19-3.3V-Pad6)") (class "Default")
      (node (ref "U19") (pin "6") (pinfunction "3.3V_6") (pintype "passive"))
    )
    (net (code "169") (name "unconnected-(U19-nc-Pad1)") (class "Default")
      (node (ref "U19") (pin "1") (pinfunction "nc_1") (pintype "passive"))
    )
    (net (code "170") (name "unconnected-(U20-D15-Pad18)") (class "Default")
      (node (ref "U20") (pin "18") (pinfunction "D15_18") (pintype "passive"))
    )
    (net (code "171") (name "unconnected-(U20-VN-Pad3)") (class "Default")
      (node (ref "U20") (pin "3") (pinfunction "VN_3") (pintype "passive"))
    )
    (net (code "172") (name "unconnected-(U20-VP-Pad2)") (class "Default")
      (node (ref "U20") (pin "2") (pinfunction "VP_2") (pintype "passive"))
    )
  )
)
